# uc2950-v1.net
KiCad netlist of a schematic drawn in EAGLE
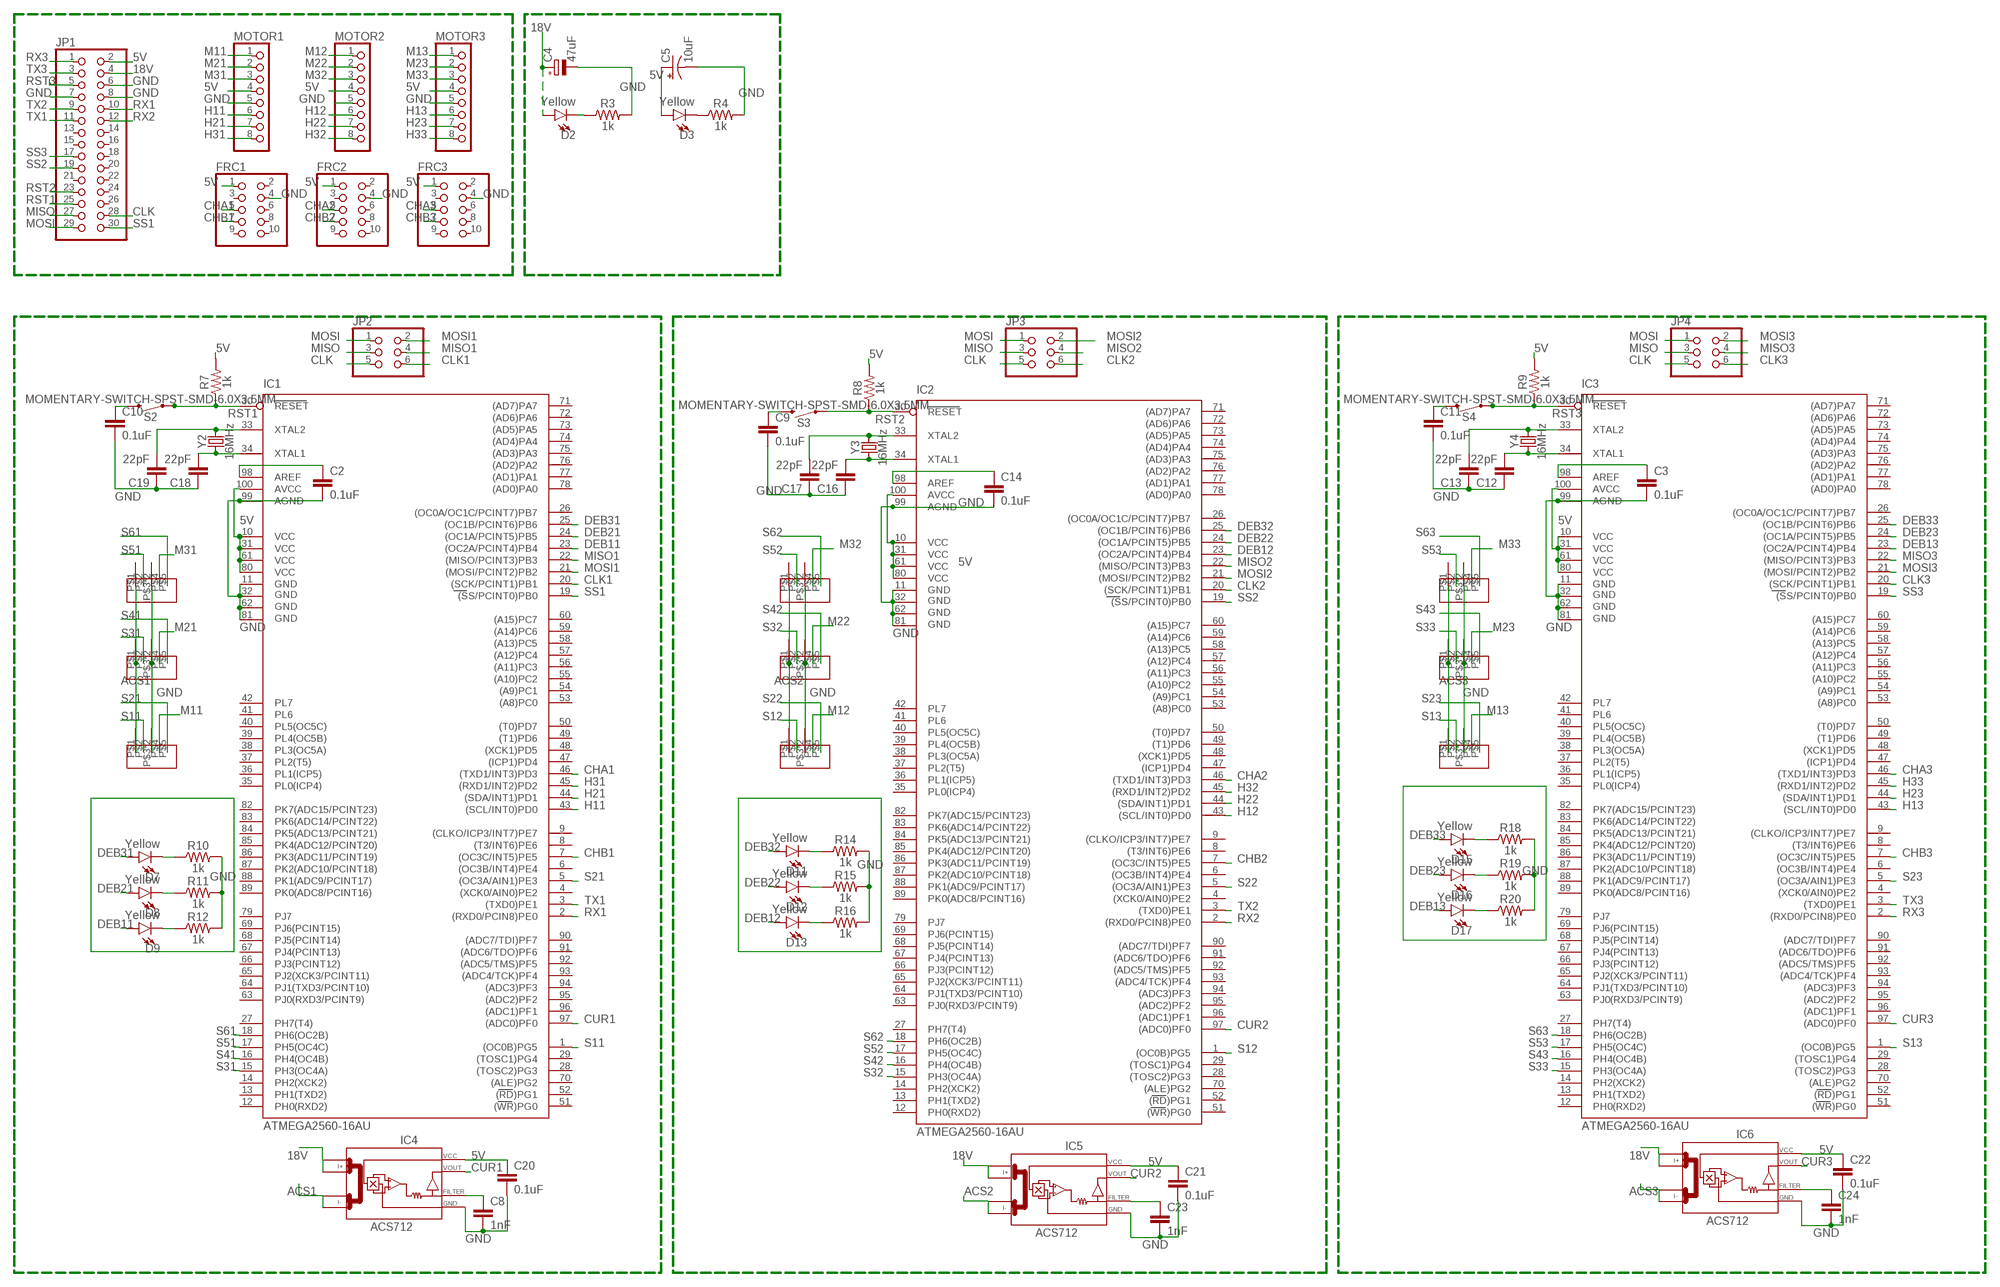
[diagram p0: schematic, sheet 1]

(export (version "E")
  (design (tool "Eeschema 10.0.6"))
  (components
    (comp (ref "C2")
      (value "0.1uF")
      (footprint "eagle-import:0603")
      (libsource (lib "eagle-import") (part "0.1UF-0603-25V-5%"))
    )
    (comp (ref "C3")
      (value "0.1uF")
      (footprint "eagle-import:0603")
      (libsource (lib "eagle-import") (part "0.1UF-0603-25V-5%"))
    )
    (comp (ref "C4")
      (value "47uF")
      (footprint "eagle-import:TAP5-60")
      (libsource (lib "eagle-import") (part "CPOL-EUTAP5-60"))
    )
    (comp (ref "C5")
      (value "10uF")
      (footprint "eagle-import:0603-POLAR")
      (libsource (lib "eagle-import") (part "10UF-POLAR-0603-6.3V-20%(TANT)"))
    )
    (comp (ref "C8")
      (value "1nF")
      (footprint "eagle-import:0603")
      (libsource (lib "eagle-import") (part "1.0NF/1000PF-0603-50V-10%"))
    )
    (comp (ref "C9")
      (value "0.1uF")
      (footprint "eagle-import:0603")
      (libsource (lib "eagle-import") (part "0.1UF-0603-25V-5%"))
    )
    (comp (ref "C10")
      (value "0.1uF")
      (footprint "eagle-import:0603")
      (libsource (lib "eagle-import") (part "0.1UF-0603-25V-5%"))
    )
    (comp (ref "C11")
      (value "0.1uF")
      (footprint "eagle-import:0603")
      (libsource (lib "eagle-import") (part "0.1UF-0603-25V-5%"))
    )
    (comp (ref "C12")
      (value "22pF")
      (footprint "eagle-import:0603")
      (libsource (lib "eagle-import") (part "22PF-0603-50V-5%"))
    )
    (comp (ref "C13")
      (value "22pF")
      (footprint "eagle-import:0603")
      (libsource (lib "eagle-import") (part "22PF-0603-50V-5%"))
    )
    (comp (ref "C14")
      (value "0.1uF")
      (footprint "eagle-import:0603")
      (libsource (lib "eagle-import") (part "0.1UF-0603-25V-5%"))
    )
    (comp (ref "C16")
      (value "22pF")
      (footprint "eagle-import:0603")
      (libsource (lib "eagle-import") (part "22PF-0603-50V-5%"))
    )
    (comp (ref "C17")
      (value "22pF")
      (footprint "eagle-import:0603")
      (libsource (lib "eagle-import") (part "22PF-0603-50V-5%"))
    )
    (comp (ref "C18")
      (value "22pF")
      (footprint "eagle-import:0603")
      (libsource (lib "eagle-import") (part "22PF-0603-50V-5%"))
    )
    (comp (ref "C19")
      (value "22pF")
      (footprint "eagle-import:0603")
      (libsource (lib "eagle-import") (part "22PF-0603-50V-5%"))
    )
    (comp (ref "C20")
      (value "0.1uF")
      (footprint "eagle-import:0603")
      (libsource (lib "eagle-import") (part "0.1UF-0603-25V-5%"))
    )
    (comp (ref "C21")
      (value "0.1uF")
      (footprint "eagle-import:0603")
      (libsource (lib "eagle-import") (part "0.1UF-0603-25V-5%"))
    )
    (comp (ref "C22")
      (value "0.1uF")
      (footprint "eagle-import:0603")
      (libsource (lib "eagle-import") (part "0.1UF-0603-25V-5%"))
    )
    (comp (ref "C23")
      (value "1nF")
      (footprint "eagle-import:0603")
      (libsource (lib "eagle-import") (part "1.0NF/1000PF-0603-50V-10%"))
    )
    (comp (ref "C24")
      (value "1nF")
      (footprint "eagle-import:0603")
      (libsource (lib "eagle-import") (part "1.0NF/1000PF-0603-50V-10%"))
    )
    (comp (ref "D2")
      (value "Yellow")
      (footprint "eagle-import:LED-0603")
      (libsource (lib "eagle-import") (part "LED-YELLOW0603"))
    )
    (comp (ref "D3")
      (value "Yellow")
      (footprint "eagle-import:LED-0603")
      (libsource (lib "eagle-import") (part "LED-YELLOW0603"))
    )
    (comp (ref "D7")
      (value "Yellow")
      (footprint "eagle-import:LED-0603")
      (libsource (lib "eagle-import") (part "LED-YELLOW0603"))
    )
    (comp (ref "D8")
      (value "Yellow")
      (footprint "eagle-import:LED-0603")
      (libsource (lib "eagle-import") (part "LED-YELLOW0603"))
    )
    (comp (ref "D9")
      (value "Yellow")
      (footprint "eagle-import:LED-0603")
      (libsource (lib "eagle-import") (part "LED-YELLOW0603"))
    )
    (comp (ref "D11")
      (value "Yellow")
      (footprint "eagle-import:LED-0603")
      (libsource (lib "eagle-import") (part "LED-YELLOW0603"))
    )
    (comp (ref "D12")
      (value "Yellow")
      (footprint "eagle-import:LED-0603")
      (libsource (lib "eagle-import") (part "LED-YELLOW0603"))
    )
    (comp (ref "D13")
      (value "Yellow")
      (footprint "eagle-import:LED-0603")
      (libsource (lib "eagle-import") (part "LED-YELLOW0603"))
    )
    (comp (ref "D15")
      (value "Yellow")
      (footprint "eagle-import:LED-0603")
      (libsource (lib "eagle-import") (part "LED-YELLOW0603"))
    )
    (comp (ref "D16")
      (value "Yellow")
      (footprint "eagle-import:LED-0603")
      (libsource (lib "eagle-import") (part "LED-YELLOW0603"))
    )
    (comp (ref "D17")
      (value "Yellow")
      (footprint "eagle-import:LED-0603")
      (libsource (lib "eagle-import") (part "LED-YELLOW0603"))
    )
    (comp (ref "FRC1")
      (value "PINHD-2X5")
      (footprint "eagle-import:2X05")
      (libsource (lib "eagle-import") (part "PINHD-2X5"))
    )
    (comp (ref "FRC2")
      (value "PINHD-2X5")
      (footprint "eagle-import:2X05")
      (libsource (lib "eagle-import") (part "PINHD-2X5"))
    )
    (comp (ref "FRC3")
      (value "PINHD-2X5")
      (footprint "eagle-import:2X05")
      (libsource (lib "eagle-import") (part "PINHD-2X5"))
    )
    (comp (ref "IC1")
      (value "ATMEGA2560-16AU")
      (footprint "eagle-import:TQFP100")
      (libsource (lib "eagle-import") (part "ATMEGAAU2560-16"))
    )
    (comp (ref "IC2")
      (value "ATMEGA2560-16AU")
      (footprint "eagle-import:TQFP100")
      (libsource (lib "eagle-import") (part "ATMEGAAU2560-16"))
    )
    (comp (ref "IC3")
      (value "ATMEGA2560-16AU")
      (footprint "eagle-import:TQFP100")
      (libsource (lib "eagle-import") (part "ATMEGAAU2560-16"))
    )
    (comp (ref "IC4")
      (value "ACS712")
      (footprint "eagle-import:SO08")
      (libsource (lib "eagle-import") (part "ACS712"))
    )
    (comp (ref "IC5")
      (value "ACS712")
      (footprint "eagle-import:SO08")
      (libsource (lib "eagle-import") (part "ACS712"))
    )
    (comp (ref "IC6")
      (value "ACS712")
      (footprint "eagle-import:SO08")
      (libsource (lib "eagle-import") (part "ACS712"))
    )
    (comp (ref "JP1")
      (value "PINHD-2X15/90")
      (footprint "eagle-import:2X15_90")
      (libsource (lib "eagle-import") (part "PINHD-2X15/90"))
    )
    (comp (ref "JP2")
      (value "PINHD-2X3")
      (footprint "eagle-import:2X03")
      (libsource (lib "eagle-import") (part "PINHD-2X3"))
    )
    (comp (ref "JP3")
      (value "PINHD-2X3")
      (footprint "eagle-import:2X03")
      (libsource (lib "eagle-import") (part "PINHD-2X3"))
    )
    (comp (ref "JP4")
      (value "PINHD-2X3")
      (footprint "eagle-import:2X03")
      (libsource (lib "eagle-import") (part "PINHD-2X3"))
    )
    (comp (ref "MIC1")
      (value "UC2950")
      (footprint "eagle-import:UC2950")
      (libsource (lib "eagle-import") (part "UC2950"))
    )
    (comp (ref "MIC2")
      (value "UC2950")
      (footprint "eagle-import:UC2950")
      (libsource (lib "eagle-import") (part "UC2950"))
    )
    (comp (ref "MIC3")
      (value "UC2950")
      (footprint "eagle-import:UC2950")
      (libsource (lib "eagle-import") (part "UC2950"))
    )
    (comp (ref "MIC4")
      (value "UC2950")
      (footprint "eagle-import:UC2950")
      (libsource (lib "eagle-import") (part "UC2950"))
    )
    (comp (ref "MIC5")
      (value "UC2950")
      (footprint "eagle-import:UC2950")
      (libsource (lib "eagle-import") (part "UC2950"))
    )
    (comp (ref "MIC6")
      (value "UC2950")
      (footprint "eagle-import:UC2950")
      (libsource (lib "eagle-import") (part "UC2950"))
    )
    (comp (ref "MIC7")
      (value "UC2950")
      (footprint "eagle-import:UC2950")
      (libsource (lib "eagle-import") (part "UC2950"))
    )
    (comp (ref "MIC8")
      (value "UC2950")
      (footprint "eagle-import:UC2950")
      (libsource (lib "eagle-import") (part "UC2950"))
    )
    (comp (ref "MIC9")
      (value "UC2950")
      (footprint "eagle-import:UC2950")
      (libsource (lib "eagle-import") (part "UC2950"))
    )
    (comp (ref "MOTOR1")
      (value "PINHD-1X8")
      (footprint "eagle-import:1X08")
      (libsource (lib "eagle-import") (part "PINHD-1X8"))
    )
    (comp (ref "MOTOR2")
      (value "PINHD-1X8")
      (footprint "eagle-import:1X08")
      (libsource (lib "eagle-import") (part "PINHD-1X8"))
    )
    (comp (ref "MOTOR3")
      (value "PINHD-1X8")
      (footprint "eagle-import:1X08")
      (libsource (lib "eagle-import") (part "PINHD-1X8"))
    )
    (comp (ref "R3")
      (value "1k")
      (footprint "eagle-import:0603")
      (libsource (lib "eagle-import") (part "1KOHM-0603-1/10W-1%"))
    )
    (comp (ref "R4")
      (value "1k")
      (footprint "eagle-import:0603")
      (libsource (lib "eagle-import") (part "1KOHM-0603-1/10W-1%"))
    )
    (comp (ref "R7")
      (value "1k")
      (footprint "eagle-import:0603")
      (libsource (lib "eagle-import") (part "1KOHM-0603-1/10W-1%"))
    )
    (comp (ref "R8")
      (value "1k")
      (footprint "eagle-import:0603")
      (libsource (lib "eagle-import") (part "1KOHM-0603-1/10W-1%"))
    )
    (comp (ref "R9")
      (value "1k")
      (footprint "eagle-import:0603")
      (libsource (lib "eagle-import") (part "1KOHM-0603-1/10W-1%"))
    )
    (comp (ref "R10")
      (value "1k")
      (footprint "eagle-import:0603")
      (libsource (lib "eagle-import") (part "1KOHM-0603-1/10W-1%"))
    )
    (comp (ref "R11")
      (value "1k")
      (footprint "eagle-import:0603")
      (libsource (lib "eagle-import") (part "1KOHM-0603-1/10W-1%"))
    )
    (comp (ref "R12")
      (value "1k")
      (footprint "eagle-import:0603")
      (libsource (lib "eagle-import") (part "1KOHM-0603-1/10W-1%"))
    )
    (comp (ref "R14")
      (value "1k")
      (footprint "eagle-import:0603")
      (libsource (lib "eagle-import") (part "1KOHM-0603-1/10W-1%"))
    )
    (comp (ref "R15")
      (value "1k")
      (footprint "eagle-import:0603")
      (libsource (lib "eagle-import") (part "1KOHM-0603-1/10W-1%"))
    )
    (comp (ref "R16")
      (value "1k")
      (footprint "eagle-import:0603")
      (libsource (lib "eagle-import") (part "1KOHM-0603-1/10W-1%"))
    )
    (comp (ref "R18")
      (value "1k")
      (footprint "eagle-import:0603")
      (libsource (lib "eagle-import") (part "1KOHM-0603-1/10W-1%"))
    )
    (comp (ref "R19")
      (value "1k")
      (footprint "eagle-import:0603")
      (libsource (lib "eagle-import") (part "1KOHM-0603-1/10W-1%"))
    )
    (comp (ref "R20")
      (value "1k")
      (footprint "eagle-import:0603")
      (libsource (lib "eagle-import") (part "1KOHM-0603-1/10W-1%"))
    )
    (comp (ref "S2")
      (value "MOMENTARY-SWITCH-SPST-SMD-6.0X3.5MM")
      (footprint "eagle-import:TACTILE_SWITCH_SMD_6.0X3.5MM")
      (libsource (lib "eagle-import") (part "MOMENTARY-SWITCH-SPST-SMD-6.0X3.5MM"))
    )
    (comp (ref "S3")
      (value "MOMENTARY-SWITCH-SPST-SMD-6.0X3.5MM")
      (footprint "eagle-import:TACTILE_SWITCH_SMD_6.0X3.5MM")
      (libsource (lib "eagle-import") (part "MOMENTARY-SWITCH-SPST-SMD-6.0X3.5MM"))
    )
    (comp (ref "S4")
      (value "MOMENTARY-SWITCH-SPST-SMD-6.0X3.5MM")
      (footprint "eagle-import:TACTILE_SWITCH_SMD_6.0X3.5MM")
      (libsource (lib "eagle-import") (part "MOMENTARY-SWITCH-SPST-SMD-6.0X3.5MM"))
    )
    (comp (ref "Y2")
      (value "16MHz")
      (footprint "eagle-import:CRYSTAL-SMD-5X3.2-4PAD")
      (libsource (lib "eagle-import") (part "CRYSTAL-16MHZSMD-5X3.2"))
    )
    (comp (ref "Y3")
      (value "16MHz")
      (footprint "eagle-import:CRYSTAL-SMD-5X3.2-4PAD")
      (libsource (lib "eagle-import") (part "CRYSTAL-16MHZSMD-5X3.2"))
    )
    (comp (ref "Y4")
      (value "16MHz")
      (footprint "eagle-import:CRYSTAL-SMD-5X3.2-4PAD")
      (libsource (lib "eagle-import") (part "CRYSTAL-16MHZSMD-5X3.2"))
    )
  )
  (nets
    (net (code "1") (name "/5V") (class "Default")
      (node (ref "C20") (pin "1") (pinfunction "1_1") (pintype "passive"))
      (node (ref "C21") (pin "1") (pinfunction "1_1") (pintype "passive"))
      (node (ref "C22") (pin "1") (pinfunction "1_1") (pintype "passive"))
      (node (ref "C5") (pin "+") (pinfunction "+_+") (pintype "passive"))
      (node (ref "D3") (pin "A") (pinfunction "A_A") (pintype "passive"))
      (node (ref "FRC1") (pin "1") (pinfunction "1_1") (pintype "passive"))
      (node (ref "FRC2") (pin "1") (pinfunction "1_1") (pintype "passive"))
      (node (ref "FRC3") (pin "1") (pinfunction "1_1") (pintype "passive"))
      (node (ref "IC1") (pin "10") (pinfunction "VCC_10") (pintype "power_in"))
      (node (ref "IC1") (pin "100") (pinfunction "AVCC_100") (pintype "power_in"))
      (node (ref "IC1") (pin "31") (pinfunction "VCC1_31") (pintype "power_in"))
      (node (ref "IC1") (pin "61") (pinfunction "VCC2_61") (pintype "power_in"))
      (node (ref "IC1") (pin "80") (pinfunction "VCC3_80") (pintype "power_in"))
      (node (ref "IC2") (pin "10") (pinfunction "VCC_10") (pintype "power_in"))
      (node (ref "IC2") (pin "100") (pinfunction "AVCC_100") (pintype "power_in"))
      (node (ref "IC2") (pin "31") (pinfunction "VCC1_31") (pintype "power_in"))
      (node (ref "IC2") (pin "61") (pinfunction "VCC2_61") (pintype "power_in"))
      (node (ref "IC2") (pin "80") (pinfunction "VCC3_80") (pintype "power_in"))
      (node (ref "IC3") (pin "10") (pinfunction "VCC_10") (pintype "power_in"))
      (node (ref "IC3") (pin "100") (pinfunction "AVCC_100") (pintype "power_in"))
      (node (ref "IC3") (pin "31") (pinfunction "VCC1_31") (pintype "power_in"))
      (node (ref "IC3") (pin "61") (pinfunction "VCC2_61") (pintype "power_in"))
      (node (ref "IC3") (pin "80") (pinfunction "VCC3_80") (pintype "power_in"))
      (node (ref "IC4") (pin "8") (pinfunction "VCC_8") (pintype "power_in"))
      (node (ref "IC5") (pin "8") (pinfunction "VCC_8") (pintype "power_in"))
      (node (ref "IC6") (pin "8") (pinfunction "VCC_8") (pintype "power_in"))
      (node (ref "JP1") (pin "2") (pinfunction "2_2") (pintype "passive"))
      (node (ref "MOTOR1") (pin "4") (pinfunction "4_4") (pintype "passive"))
      (node (ref "MOTOR2") (pin "4") (pinfunction "4_4") (pintype "passive"))
      (node (ref "MOTOR3") (pin "4") (pinfunction "4_4") (pintype "passive"))
      (node (ref "R7") (pin "2") (pinfunction "2_2") (pintype "passive"))
      (node (ref "R8") (pin "2") (pinfunction "2_2") (pintype "passive"))
      (node (ref "R9") (pin "2") (pinfunction "2_2") (pintype "passive"))
    )
    (net (code "2") (name "/18V") (class "Default")
      (node (ref "C4") (pin "+") (pinfunction "+_+") (pintype "passive"))
      (node (ref "D2") (pin "A") (pinfunction "A_A") (pintype "passive"))
      (node (ref "IC4") (pin "1") (pinfunction "I+_0_1") (pintype "bidirectional"))
      (node (ref "IC5") (pin "1") (pinfunction "I+_0_1") (pintype "bidirectional"))
      (node (ref "IC6") (pin "1") (pinfunction "I+_0_1") (pintype "bidirectional"))
      (node (ref "JP1") (pin "4") (pinfunction "4_4") (pintype "passive"))
    )
    (net (code "3") (name "/ACS1") (class "Default")
      (node (ref "IC4") (pin "3") (pinfunction "I-_0_3") (pintype "bidirectional"))
      (node (ref "MIC1") (pin "P$1") (pinfunction "P$1_P$1") (pintype "bidirectional"))
      (node (ref "MIC2") (pin "P$1") (pinfunction "P$1_P$1") (pintype "bidirectional"))
      (node (ref "MIC3") (pin "P$1") (pinfunction "P$1_P$1") (pintype "bidirectional"))
    )
    (net (code "4") (name "/ACS2") (class "Default")
      (node (ref "IC5") (pin "3") (pinfunction "I-_0_3") (pintype "bidirectional"))
      (node (ref "MIC4") (pin "P$1") (pinfunction "P$1_P$1") (pintype "bidirectional"))
      (node (ref "MIC5") (pin "P$1") (pinfunction "P$1_P$1") (pintype "bidirectional"))
      (node (ref "MIC6") (pin "P$1") (pinfunction "P$1_P$1") (pintype "bidirectional"))
    )
    (net (code "5") (name "/ACS3") (class "Default")
      (node (ref "IC6") (pin "3") (pinfunction "I-_0_3") (pintype "bidirectional"))
      (node (ref "MIC7") (pin "P$1") (pinfunction "P$1_P$1") (pintype "bidirectional"))
      (node (ref "MIC8") (pin "P$1") (pinfunction "P$1_P$1") (pintype "bidirectional"))
      (node (ref "MIC9") (pin "P$1") (pinfunction "P$1_P$1") (pintype "bidirectional"))
    )
    (net (code "6") (name "/CHA1") (class "Default")
      (node (ref "FRC1") (pin "5") (pinfunction "5_5") (pintype "passive"))
      (node (ref "IC1") (pin "46") (pinfunction "(TXD1/INT3)PD3_46") (pintype "bidirectional"))
    )
    (net (code "7") (name "/CHA2") (class "Default")
      (node (ref "FRC2") (pin "5") (pinfunction "5_5") (pintype "passive"))
      (node (ref "IC2") (pin "46") (pinfunction "(TXD1/INT3)PD3_46") (pintype "bidirectional"))
    )
    (net (code "8") (name "/CHA3") (class "Default")
      (node (ref "FRC3") (pin "5") (pinfunction "5_5") (pintype "passive"))
      (node (ref "IC3") (pin "46") (pinfunction "(TXD1/INT3)PD3_46") (pintype "bidirectional"))
    )
    (net (code "9") (name "/CHB1") (class "Default")
      (node (ref "FRC1") (pin "7") (pinfunction "7_7") (pintype "passive"))
      (node (ref "IC1") (pin "7") (pinfunction "(OC3C/INT5)PE5_7") (pintype "bidirectional"))
    )
    (net (code "10") (name "/CHB2") (class "Default")
      (node (ref "FRC2") (pin "7") (pinfunction "7_7") (pintype "passive"))
      (node (ref "IC2") (pin "7") (pinfunction "(OC3C/INT5)PE5_7") (pintype "bidirectional"))
    )
    (net (code "11") (name "/CHB3") (class "Default")
      (node (ref "FRC3") (pin "7") (pinfunction "7_7") (pintype "passive"))
      (node (ref "IC3") (pin "7") (pinfunction "(OC3C/INT5)PE5_7") (pintype "bidirectional"))
    )
    (net (code "12") (name "/CLK") (class "Default")
      (node (ref "JP1") (pin "28") (pinfunction "28_28") (pintype "passive"))
      (node (ref "JP2") (pin "5") (pinfunction "5_5") (pintype "passive"))
      (node (ref "JP3") (pin "5") (pinfunction "5_5") (pintype "passive"))
      (node (ref "JP4") (pin "5") (pinfunction "5_5") (pintype "passive"))
    )
    (net (code "13") (name "/CLK1") (class "Default")
      (node (ref "IC1") (pin "20") (pinfunction "(SCK/PCINT1)PB1_20") (pintype "bidirectional"))
      (node (ref "JP2") (pin "6") (pinfunction "6_6") (pintype "passive"))
    )
    (net (code "14") (name "/CLK2") (class "Default")
      (node (ref "IC2") (pin "20") (pinfunction "(SCK/PCINT1)PB1_20") (pintype "bidirectional"))
      (node (ref "JP3") (pin "6") (pinfunction "6_6") (pintype "passive"))
    )
    (net (code "15") (name "/CLK3") (class "Default")
      (node (ref "IC3") (pin "20") (pinfunction "(SCK/PCINT1)PB1_20") (pintype "bidirectional"))
      (node (ref "JP4") (pin "6") (pinfunction "6_6") (pintype "passive"))
    )
    (net (code "16") (name "/CUR1") (class "Default")
      (node (ref "IC1") (pin "97") (pinfunction "(ADC0)PF0_97") (pintype "bidirectional"))
      (node (ref "IC4") (pin "7") (pinfunction "VOUT_7") (pintype "output"))
    )
    (net (code "17") (name "/CUR2") (class "Default")
      (node (ref "IC2") (pin "97") (pinfunction "(ADC0)PF0_97") (pintype "bidirectional"))
      (node (ref "IC5") (pin "7") (pinfunction "VOUT_7") (pintype "output"))
    )
    (net (code "18") (name "/CUR3") (class "Default")
      (node (ref "IC3") (pin "97") (pinfunction "(ADC0)PF0_97") (pintype "bidirectional"))
      (node (ref "IC6") (pin "7") (pinfunction "VOUT_7") (pintype "output"))
    )
    (net (code "19") (name "/DEB11") (class "Default")
      (node (ref "D9") (pin "A") (pinfunction "A_A") (pintype "passive"))
      (node (ref "IC1") (pin "23") (pinfunction "(OC2A/PCINT4)PB4_23") (pintype "bidirectional"))
    )
    (net (code "20") (name "/DEB12") (class "Default")
      (node (ref "D13") (pin "A") (pinfunction "A_A") (pintype "passive"))
      (node (ref "IC2") (pin "23") (pinfunction "(OC2A/PCINT4)PB4_23") (pintype "bidirectional"))
    )
    (net (code "21") (name "/DEB13") (class "Default")
      (node (ref "D17") (pin "A") (pinfunction "A_A") (pintype "passive"))
      (node (ref "IC3") (pin "23") (pinfunction "(OC2A/PCINT4)PB4_23") (pintype "bidirectional"))
    )
    (net (code "22") (name "/DEB21") (class "Default")
      (node (ref "D8") (pin "A") (pinfunction "A_A") (pintype "passive"))
      (node (ref "IC1") (pin "24") (pinfunction "(OC1A/PCINT5)PB5_24") (pintype "bidirectional"))
    )
    (net (code "23") (name "/DEB22") (class "Default")
      (node (ref "D12") (pin "A") (pinfunction "A_A") (pintype "passive"))
      (node (ref "IC2") (pin "24") (pinfunction "(OC1A/PCINT5)PB5_24") (pintype "bidirectional"))
    )
    (net (code "24") (name "/DEB23") (class "Default")
      (node (ref "D16") (pin "A") (pinfunction "A_A") (pintype "passive"))
      (node (ref "IC3") (pin "24") (pinfunction "(OC1A/PCINT5)PB5_24") (pintype "bidirectional"))
    )
    (net (code "25") (name "/DEB31") (class "Default")
      (node (ref "D7") (pin "A") (pinfunction "A_A") (pintype "passive"))
      (node (ref "IC1") (pin "25") (pinfunction "(OC1B/PCINT6)PB6_25") (pintype "bidirectional"))
    )
    (net (code "26") (name "/DEB32") (class "Default")
      (node (ref "D11") (pin "A") (pinfunction "A_A") (pintype "passive"))
      (node (ref "IC2") (pin "25") (pinfunction "(OC1B/PCINT6)PB6_25") (pintype "bidirectional"))
    )
    (net (code "27") (name "/DEB33") (class "Default")
      (node (ref "D15") (pin "A") (pinfunction "A_A") (pintype "passive"))
      (node (ref "IC3") (pin "25") (pinfunction "(OC1B/PCINT6)PB6_25") (pintype "bidirectional"))
    )
    (net (code "28") (name "/GND") (class "Default")
      (node (ref "C10") (pin "2") (pinfunction "2_2") (pintype "passive"))
      (node (ref "C11") (pin "2") (pinfunction "2_2") (pintype "passive"))
      (node (ref "C12") (pin "1") (pinfunction "1_1") (pintype "passive"))
      (node (ref "C13") (pin "1") (pinfunction "1_1") (pintype "passive"))
      (node (ref "C14") (pin "2") (pinfunction "2_2") (pintype "passive"))
      (node (ref "C16") (pin "1") (pinfunction "1_1") (pintype "passive"))
      (node (ref "C17") (pin "1") (pinfunction "1_1") (pintype "passive"))
      (node (ref "C18") (pin "1") (pinfunction "1_1") (pintype "passive"))
      (node (ref "C19") (pin "1") (pinfunction "1_1") (pintype "passive"))
      (node (ref "C2") (pin "2") (pinfunction "2_2") (pintype "passive"))
      (node (ref "C20") (pin "2") (pinfunction "2_2") (pintype "passive"))
      (node (ref "C21") (pin "2") (pinfunction "2_2") (pintype "passive"))
      (node (ref "C22") (pin "2") (pinfunction "2_2") (pintype "passive"))
      (node (ref "C23") (pin "2") (pinfunction "2_2") (pintype "passive"))
      (node (ref "C24") (pin "2") (pinfunction "2_2") (pintype "passive"))
      (node (ref "C3") (pin "2") (pinfunction "2_2") (pintype "passive"))
      (node (ref "C4") (pin "-") (pinfunction "-_-") (pintype "passive"))
      (node (ref "C5") (pin "-") (pinfunction "-_-") (pintype "passive"))
      (node (ref "C8") (pin "2") (pinfunction "2_2") (pintype "passive"))
      (node (ref "C9") (pin "2") (pinfunction "2_2") (pintype "passive"))
      (node (ref "FRC1") (pin "4") (pinfunction "4_4") (pintype "passive"))
      (node (ref "FRC2") (pin "4") (pinfunction "4_4") (pintype "passive"))
      (node (ref "FRC3") (pin "4") (pinfunction "4_4") (pintype "passive"))
      (node (ref "IC1") (pin "11") (pinfunction "GND_11") (pintype "power_in"))
      (node (ref "IC1") (pin "32") (pinfunction "GND1_32") (pintype "power_in"))
      (node (ref "IC1") (pin "62") (pinfunction "GND2_62") (pintype "power_in"))
      (node (ref "IC1") (pin "81") (pinfunction "GND3_81") (pintype "power_in"))
      (node (ref "IC1") (pin "99") (pinfunction "AGND_99") (pintype "power_in"))
      (node (ref "IC2") (pin "11") (pinfunction "GND_11") (pintype "power_in"))
      (node (ref "IC2") (pin "32") (pinfunction "GND1_32") (pintype "power_in"))
      (node (ref "IC2") (pin "62") (pinfunction "GND2_62") (pintype "power_in"))
      (node (ref "IC2") (pin "81") (pinfunction "GND3_81") (pintype "power_in"))
      (node (ref "IC2") (pin "99") (pinfunction "AGND_99") (pintype "power_in"))
      (node (ref "IC3") (pin "11") (pinfunction "GND_11") (pintype "power_in"))
      (node (ref "IC3") (pin "32") (pinfunction "GND1_32") (pintype "power_in"))
      (node (ref "IC3") (pin "62") (pinfunction "GND2_62") (pintype "power_in"))
      (node (ref "IC3") (pin "81") (pinfunction "GND3_81") (pintype "power_in"))
      (node (ref "IC3") (pin "99") (pinfunction "AGND_99") (pintype "power_in"))
      (node (ref "IC4") (pin "5") (pinfunction "GND_5") (pintype "power_in"))
      (node (ref "IC5") (pin "5") (pinfunction "GND_5") (pintype "power_in"))
      (node (ref "IC6") (pin "5") (pinfunction "GND_5") (pintype "power_in"))
      (node (ref "JP1") (pin "6") (pinfunction "6_6") (pintype "passive"))
      (node (ref "JP1") (pin "7") (pinfunction "7_7") (pintype "passive"))
      (node (ref "JP1") (pin "8") (pinfunction "8_8") (pintype "passive"))
      (node (ref "MIC1") (pin "P$3") (pinfunction "P$3_P$3") (pintype "bidirectional"))
      (node (ref "MIC1") (pin "P$6") (pinfunction "P$3_P$6") (pintype "bidirectional"))
      (node (ref "MIC2") (pin "P$3") (pinfunction "P$3_P$3") (pintype "bidirectional"))
      (node (ref "MIC2") (pin "P$6") (pinfunction "P$3_P$6") (pintype "bidirectional"))
      (node (ref "MIC3") (pin "P$3") (pinfunction "P$3_P$3") (pintype "bidirectional"))
      (node (ref "MIC3") (pin "P$6") (pinfunction "P$3_P$6") (pintype "bidirectional"))
      (node (ref "MIC4") (pin "P$3") (pinfunction "P$3_P$3") (pintype "bidirectional"))
      (node (ref "MIC4") (pin "P$6") (pinfunction "P$3_P$6") (pintype "bidirectional"))
      (node (ref "MIC5") (pin "P$3") (pinfunction "P$3_P$3") (pintype "bidirectional"))
      (node (ref "MIC5") (pin "P$6") (pinfunction "P$3_P$6") (pintype "bidirectional"))
      (node (ref "MIC6") (pin "P$3") (pinfunction "P$3_P$3") (pintype "bidirectional"))
      (node (ref "MIC6") (pin "P$6") (pinfunction "P$3_P$6") (pintype "bidirectional"))
      (node (ref "MIC7") (pin "P$3") (pinfunction "P$3_P$3") (pintype "bidirectional"))
      (node (ref "MIC7") (pin "P$6") (pinfunction "P$3_P$6") (pintype "bidirectional"))
      (node (ref "MIC8") (pin "P$3") (pinfunction "P$3_P$3") (pintype "bidirectional"))
      (node (ref "MIC8") (pin "P$6") (pinfunction "P$3_P$6") (pintype "bidirectional"))
      (node (ref "MIC9") (pin "P$3") (pinfunction "P$3_P$3") (pintype "bidirectional"))
      (node (ref "MIC9") (pin "P$6") (pinfunction "P$3_P$6") (pintype "bidirectional"))
      (node (ref "MOTOR1") (pin "5") (pinfunction "5_5") (pintype "passive"))
      (node (ref "MOTOR2") (pin "5") (pinfunction "5_5") (pintype "passive"))
      (node (ref "MOTOR3") (pin "5") (pinfunction "5_5") (pintype "passive"))
      (node (ref "R10") (pin "2") (pinfunction "2_2") (pintype "passive"))
      (node (ref "R11") (pin "2") (pinfunction "2_2") (pintype "passive"))
      (node (ref "R12") (pin "2") (pinfunction "2_2") (pintype "passive"))
      (node (ref "R14") (pin "2") (pinfunction "2_2") (pintype "passive"))
      (node (ref "R15") (pin "2") (pinfunction "2_2") (pintype "passive"))
      (node (ref "R16") (pin "2") (pinfunction "2_2") (pintype "passive"))
      (node (ref "R18") (pin "2") (pinfunction "2_2") (pintype "passive"))
      (node (ref "R19") (pin "2") (pinfunction "2_2") (pintype "passive"))
      (node (ref "R20") (pin "2") (pinfunction "2_2") (pintype "passive"))
      (node (ref "R3") (pin "2") (pinfunction "2_2") (pintype "passive"))
      (node (ref "R4") (pin "2") (pinfunction "2_2") (pintype "passive"))
    )
    (net (code "29") (name "/H11") (class "Default")
      (node (ref "IC1") (pin "43") (pinfunction "(SCL/INT0)PD0_43") (pintype "bidirectional"))
      (node (ref "MOTOR1") (pin "6") (pinfunction "6_6") (pintype "passive"))
    )
    (net (code "30") (name "/H12") (class "Default")
      (node (ref "IC2") (pin "43") (pinfunction "(SCL/INT0)PD0_43") (pintype "bidirectional"))
      (node (ref "MOTOR2") (pin "6") (pinfunction "6_6") (pintype "passive"))
    )
    (net (code "31") (name "/H13") (class "Default")
      (node (ref "IC3") (pin "43") (pinfunction "(SCL/INT0)PD0_43") (pintype "bidirectional"))
      (node (ref "MOTOR3") (pin "6") (pinfunction "6_6") (pintype "passive"))
    )
    (net (code "32") (name "/H21") (class "Default")
      (node (ref "IC1") (pin "44") (pinfunction "(SDA/INT1)PD1_44") (pintype "bidirectional"))
      (node (ref "MOTOR1") (pin "7") (pinfunction "7_7") (pintype "passive"))
    )
    (net (code "33") (name "/H22") (class "Default")
      (node (ref "IC2") (pin "44") (pinfunction "(SDA/INT1)PD1_44") (pintype "bidirectional"))
      (node (ref "MOTOR2") (pin "7") (pinfunction "7_7") (pintype "passive"))
    )
    (net (code "34") (name "/H23") (class "Default")
      (node (ref "IC3") (pin "44") (pinfunction "(SDA/INT1)PD1_44") (pintype "bidirectional"))
      (node (ref "MOTOR3") (pin "7") (pinfunction "7_7") (pintype "passive"))
    )
    (net (code "35") (name "/H31") (class "Default")
      (node (ref "IC1") (pin "45") (pinfunction "(RXD1/INT2)PD2_45") (pintype "bidirectional"))
      (node (ref "MOTOR1") (pin "8") (pinfunction "8_8") (pintype "passive"))
    )
    (net (code "36") (name "/H32") (class "Default")
      (node (ref "IC2") (pin "45") (pinfunction "(RXD1/INT2)PD2_45") (pintype "bidirectional"))
      (node (ref "MOTOR2") (pin "8") (pinfunction "8_8") (pintype "passive"))
    )
    (net (code "37") (name "/H33") (class "Default")
      (node (ref "IC3") (pin "45") (pinfunction "(RXD1/INT2)PD2_45") (pintype "bidirectional"))
      (node (ref "MOTOR3") (pin "8") (pinfunction "8_8") (pintype "passive"))
    )
    (net (code "38") (name "/M11") (class "Default")
      (node (ref "MIC3") (pin "P$4") (pinfunction "P$4_P$4") (pintype "bidirectional"))
      (node (ref "MOTOR1") (pin "1") (pinfunction "1_1") (pintype "passive"))
    )
    (net (code "39") (name "/M12") (class "Default")
      (node (ref "MIC6") (pin "P$4") (pinfunction "P$4_P$4") (pintype "bidirectional"))
      (node (ref "MOTOR2") (pin "1") (pinfunction "1_1") (pintype "passive"))
    )
    (net (code "40") (name "/M13") (class "Default")
      (node (ref "MIC7") (pin "P$4") (pinfunction "P$4_P$4") (pintype "bidirectional"))
      (node (ref "MOTOR3") (pin "1") (pinfunction "1_1") (pintype "passive"))
    )
    (net (code "41") (name "/M21") (class "Default")
      (node (ref "MIC2") (pin "P$4") (pinfunction "P$4_P$4") (pintype "bidirectional"))
      (node (ref "MOTOR1") (pin "2") (pinfunction "2_2") (pintype "passive"))
    )
    (net (code "42") (name "/M22") (class "Default")
      (node (ref "MIC5") (pin "P$4") (pinfunction "P$4_P$4") (pintype "bidirectional"))
      (node (ref "MOTOR2") (pin "2") (pinfunction "2_2") (pintype "passive"))
    )
    (net (code "43") (name "/M23") (class "Default")
      (node (ref "MIC8") (pin "P$4") (pinfunction "P$4_P$4") (pintype "bidirectional"))
      (node (ref "MOTOR3") (pin "2") (pinfunction "2_2") (pintype "passive"))
    )
    (net (code "44") (name "/M31") (class "Default")
      (node (ref "MIC1") (pin "P$4") (pinfunction "P$4_P$4") (pintype "bidirectional"))
      (node (ref "MOTOR1") (pin "3") (pinfunction "3_3") (pintype "passive"))
    )
    (net (code "45") (name "/M32") (class "Default")
      (node (ref "MIC4") (pin "P$4") (pinfunction "P$4_P$4") (pintype "bidirectional"))
      (node (ref "MOTOR2") (pin "3") (pinfunction "3_3") (pintype "passive"))
    )
    (net (code "46") (name "/M33") (class "Default")
      (node (ref "MIC9") (pin "P$4") (pinfunction "P$4_P$4") (pintype "bidirectional"))
      (node (ref "MOTOR3") (pin "3") (pinfunction "3_3") (pintype "passive"))
    )
    (net (code "47") (name "/MISO") (class "Default")
      (node (ref "JP1") (pin "27") (pinfunction "27_27") (pintype "passive"))
      (node (ref "JP2") (pin "3") (pinfunction "3_3") (pintype "passive"))
      (node (ref "JP3") (pin "3") (pinfunction "3_3") (pintype "passive"))
      (node (ref "JP4") (pin "3") (pinfunction "3_3") (pintype "passive"))
    )
    (net (code "48") (name "/MISO1") (class "Default")
      (node (ref "IC1") (pin "22") (pinfunction "(MISO/PCINT3)PB3_22") (pintype "bidirectional"))
      (node (ref "JP2") (pin "4") (pinfunction "4_4") (pintype "passive"))
    )
    (net (code "49") (name "/MISO2") (class "Default")
      (node (ref "IC2") (pin "22") (pinfunction "(MISO/PCINT3)PB3_22") (pintype "bidirectional"))
      (node (ref "JP3") (pin "4") (pinfunction "4_4") (pintype "passive"))
    )
    (net (code "50") (name "/MISO3") (class "Default")
      (node (ref "IC3") (pin "22") (pinfunction "(MISO/PCINT3)PB3_22") (pintype "bidirectional"))
      (node (ref "JP4") (pin "4") (pinfunction "4_4") (pintype "passive"))
    )
    (net (code "51") (name "/MOSI") (class "Default")
      (node (ref "JP1") (pin "29") (pinfunction "29_29") (pintype "passive"))
      (node (ref "JP2") (pin "1") (pinfunction "1_1") (pintype "passive"))
      (node (ref "JP3") (pin "1") (pinfunction "1_1") (pintype "passive"))
      (node (ref "JP4") (pin "1") (pinfunction "1_1") (pintype "passive"))
    )
    (net (code "52") (name "/MOSI1") (class "Default")
      (node (ref "IC1") (pin "21") (pinfunction "(MOSI/PCINT2)PB2_21") (pintype "bidirectional"))
      (node (ref "JP2") (pin "2") (pinfunction "2_2") (pintype "passive"))
    )
    (net (code "53") (name "/MOSI2") (class "Default")
      (node (ref "IC2") (pin "21") (pinfunction "(MOSI/PCINT2)PB2_21") (pintype "bidirectional"))
      (node (ref "JP3") (pin "2") (pinfunction "2_2") (pintype "passive"))
    )
    (net (code "54") (name "/MOSI3") (class "Default")
      (node (ref "IC3") (pin "21") (pinfunction "(MOSI/PCINT2)PB2_21") (pintype "bidirectional"))
      (node (ref "JP4") (pin "2") (pinfunction "2_2") (pintype "passive"))
    )
    (net (code "55") (name "/RST1") (class "Default")
      (node (ref "IC1") (pin "30") (pinfunction "RESET_30") (pintype "input"))
      (node (ref "JP1") (pin "25") (pinfunction "25_25") (pintype "passive"))
      (node (ref "R7") (pin "1") (pinfunction "1_1") (pintype "passive"))
      (node (ref "S2") (pin "1") (pinfunction "1_1") (pintype "passive"))
    )
    (net (code "56") (name "/RST2") (class "Default")
      (node (ref "IC2") (pin "30") (pinfunction "RESET_30") (pintype "input"))
      (node (ref "JP1") (pin "23") (pinfunction "23_23") (pintype "passive"))
      (node (ref "R8") (pin "1") (pinfunction "1_1") (pintype "passive"))
      (node (ref "S3") (pin "1") (pinfunction "1_1") (pintype "passive"))
    )
    (net (code "57") (name "/RST3") (class "Default")
      (node (ref "IC3") (pin "30") (pinfunction "RESET_30") (pintype "input"))
      (node (ref "JP1") (pin "5") (pinfunction "5_5") (pintype "passive"))
      (node (ref "R9") (pin "1") (pinfunction "1_1") (pintype "passive"))
      (node (ref "S4") (pin "1") (pinfunction "1_1") (pintype "passive"))
    )
    (net (code "58") (name "/RX1") (class "Default")
      (node (ref "IC1") (pin "2") (pinfunction "(RXD0/PCIN8)PE0_2") (pintype "bidirectional"))
      (node (ref "JP1") (pin "10") (pinfunction "10_10") (pintype "passive"))
    )
    (net (code "59") (name "/RX2") (class "Default")
      (node (ref "IC2") (pin "2") (pinfunction "(RXD0/PCIN8)PE0_2") (pintype "bidirectional"))
      (node (ref "JP1") (pin "12") (pinfunction "12_12") (pintype "passive"))
    )
    (net (code "60") (name "/RX3") (class "Default")
      (node (ref "IC3") (pin "2") (pinfunction "(RXD0/PCIN8)PE0_2") (pintype "bidirectional"))
      (node (ref "JP1") (pin "1") (pinfunction "1_1") (pintype "passive"))
    )
    (net (code "61") (name "/S11") (class "Default")
      (node (ref "IC1") (pin "1") (pinfunction "(OC0B)PG5_1") (pintype "bidirectional"))
      (node (ref "MIC3") (pin "P$2") (pinfunction "P$2_P$2") (pintype "bidirectional"))
    )
    (net (code "62") (name "/S12") (class "Default")
      (node (ref "IC2") (pin "1") (pinfunction "(OC0B)PG5_1") (pintype "bidirectional"))
      (node (ref "MIC6") (pin "P$2") (pinfunction "P$2_P$2") (pintype "bidirectional"))
    )
    (net (code "63") (name "/S13") (class "Default")
      (node (ref "IC3") (pin "1") (pinfunction "(OC0B)PG5_1") (pintype "bidirectional"))
      (node (ref "MIC7") (pin "P$2") (pinfunction "P$2_P$2") (pintype "bidirectional"))
    )
    (net (code "64") (name "/S21") (class "Default")
      (node (ref "IC1") (pin "5") (pinfunction "(OC3A/AIN1)PE3_5") (pintype "bidirectional"))
      (node (ref "MIC3") (pin "P$5") (pinfunction "P$5_P$5") (pintype "bidirectional"))
    )
    (net (code "65") (name "/S22") (class "Default")
      (node (ref "IC2") (pin "5") (pinfunction "(OC3A/AIN1)PE3_5") (pintype "bidirectional"))
      (node (ref "MIC6") (pin "P$5") (pinfunction "P$5_P$5") (pintype "bidirectional"))
    )
    (net (code "66") (name "/S23") (class "Default")
      (node (ref "IC3") (pin "5") (pinfunction "(OC3A/AIN1)PE3_5") (pintype "bidirectional"))
      (node (ref "MIC7") (pin "P$5") (pinfunction "P$5_P$5") (pintype "bidirectional"))
    )
    (net (code "67") (name "/S31") (class "Default")
      (node (ref "IC1") (pin "15") (pinfunction "PH3(OC4A)_15") (pintype "bidirectional"))
      (node (ref "MIC2") (pin "P$2") (pinfunction "P$2_P$2") (pintype "bidirectional"))
    )
    (net (code "68") (name "/S32") (class "Default")
      (node (ref "IC2") (pin "15") (pinfunction "PH3(OC4A)_15") (pintype "bidirectional"))
      (node (ref "MIC5") (pin "P$2") (pinfunction "P$2_P$2") (pintype "bidirectional"))
    )
    (net (code "69") (name "/S33") (class "Default")
      (node (ref "IC3") (pin "15") (pinfunction "PH3(OC4A)_15") (pintype "bidirectional"))
      (node (ref "MIC8") (pin "P$2") (pinfunction "P$2_P$2") (pintype "bidirectional"))
    )
    (net (code "70") (name "/S41") (class "Default")
      (node (ref "IC1") (pin "16") (pinfunction "PH4(OC4B)_16") (pintype "bidirectional"))
      (node (ref "MIC2") (pin "P$5") (pinfunction "P$5_P$5") (pintype "bidirectional"))
    )
    (net (code "71") (name "/S42") (class "Default")
      (node (ref "IC2") (pin "16") (pinfunction "PH4(OC4B)_16") (pintype "bidirectional"))
      (node (ref "MIC5") (pin "P$5") (pinfunction "P$5_P$5") (pintype "bidirectional"))
    )
    (net (code "72") (name "/S43") (class "Default")
      (node (ref "IC3") (pin "16") (pinfunction "PH4(OC4B)_16") (pintype "bidirectional"))
      (node (ref "MIC8") (pin "P$5") (pinfunction "P$5_P$5") (pintype "bidirectional"))
    )
    (net (code "73") (name "/S51") (class "Default")
      (node (ref "IC1") (pin "17") (pinfunction "PH5(OC4C)_17") (pintype "bidirectional"))
      (node (ref "MIC1") (pin "P$2") (pinfunction "P$2_P$2") (pintype "bidirectional"))
    )
    (net (code "74") (name "/S52") (class "Default")
      (node (ref "IC2") (pin "17") (pinfunction "PH5(OC4C)_17") (pintype "bidirectional"))
      (node (ref "MIC4") (pin "P$2") (pinfunction "P$2_P$2") (pintype "bidirectional"))
    )
    (net (code "75") (name "/S53") (class "Default")
      (node (ref "IC3") (pin "17") (pinfunction "PH5(OC4C)_17") (pintype "bidirectional"))
      (node (ref "MIC9") (pin "P$2") (pinfunction "P$2_P$2") (pintype "bidirectional"))
    )
    (net (code "76") (name "/S61") (class "Default")
      (node (ref "IC1") (pin "18") (pinfunction "PH6(OC2B)_18") (pintype "bidirectional"))
      (node (ref "MIC1") (pin "P$5") (pinfunction "P$5_P$5") (pintype "bidirectional"))
    )
    (net (code "77") (name "/S62") (class "Default")
      (node (ref "IC2") (pin "18") (pinfunction "PH6(OC2B)_18") (pintype "bidirectional"))
      (node (ref "MIC4") (pin "P$5") (pinfunction "P$5_P$5") (pintype "bidirectional"))
    )
    (net (code "78") (name "/S63") (class "Default")
      (node (ref "IC3") (pin "18") (pinfunction "PH6(OC2B)_18") (pintype "bidirectional"))
      (node (ref "MIC9") (pin "P$5") (pinfunction "P$5_P$5") (pintype "bidirectional"))
    )
    (net (code "79") (name "/SS1") (class "Default")
      (node (ref "IC1") (pin "19") (pinfunction "(SS/PCINT0)PB0_19") (pintype "bidirectional"))
      (node (ref "JP1") (pin "30") (pinfunction "30_30") (pintype "passive"))
    )
    (net (code "80") (name "/SS2") (class "Default")
      (node (ref "IC2") (pin "19") (pinfunction "(SS/PCINT0)PB0_19") (pintype "bidirectional"))
      (node (ref "JP1") (pin "19") (pinfunction "19_19") (pintype "passive"))
    )
    (net (code "81") (name "/SS3") (class "Default")
      (node (ref "IC3") (pin "19") (pinfunction "(SS/PCINT0)PB0_19") (pintype "bidirectional"))
      (node (ref "JP1") (pin "17") (pinfunction "17_17") (pintype "passive"))
    )
    (net (code "82") (name "/TX1") (class "Default")
      (node (ref "IC1") (pin "3") (pinfunction "(TXD0)PE1_3") (pintype "bidirectional"))
      (node (ref "JP1") (pin "11") (pinfunction "11_11") (pintype "passive"))
    )
    (net (code "83") (name "/TX2") (class "Default")
      (node (ref "IC2") (pin "3") (pinfunction "(TXD0)PE1_3") (pintype "bidirectional"))
      (node (ref "JP1") (pin "9") (pinfunction "9_9") (pintype "passive"))
    )
    (net (code "84") (name "/TX3") (class "Default")
      (node (ref "IC3") (pin "3") (pinfunction "(TXD0)PE1_3") (pintype "bidirectional"))
      (node (ref "JP1") (pin "3") (pinfunction "3_3") (pintype "passive"))
    )
    (net (code "85") (name "Net-(C9-Pad1)") (class "Default")
      (node (ref "C9") (pin "1") (pinfunction "1_1") (pintype "passive"))
      (node (ref "S3") (pin "2") (pinfunction "2_2") (pintype "passive"))
    )
    (net (code "86") (name "Net-(C10-Pad1)") (class "Default")
      (node (ref "C10") (pin "1") (pinfunction "1_1") (pintype "passive"))
      (node (ref "S2") (pin "2") (pinfunction "2_2") (pintype "passive"))
    )
    (net (code "87") (name "Net-(C11-Pad1)") (class "Default")
      (node (ref "C11") (pin "1") (pinfunction "1_1") (pintype "passive"))
      (node (ref "S4") (pin "2") (pinfunction "2_2") (pintype "passive"))
    )
    (net (code "88") (name "Net-(D2-PadC)") (class "Default")
      (node (ref "D2") (pin "C") (pinfunction "C_C") (pintype "passive"))
      (node (ref "R3") (pin "1") (pinfunction "1_1") (pintype "passive"))
    )
    (net (code "89") (name "Net-(D3-PadC)") (class "Default")
      (node (ref "D3") (pin "C") (pinfunction "C_C") (pintype "passive"))
      (node (ref "R4") (pin "1") (pinfunction "1_1") (pintype "passive"))
    )
    (net (code "90") (name "Net-(D7-PadC)") (class "Default")
      (node (ref "D7") (pin "C") (pinfunction "C_C") (pintype "passive"))
      (node (ref "R10") (pin "1") (pinfunction "1_1") (pintype "passive"))
    )
    (net (code "91") (name "Net-(D8-PadC)") (class "Default")
      (node (ref "D8") (pin "C") (pinfunction "C_C") (pintype "passive"))
      (node (ref "R11") (pin "1") (pinfunction "1_1") (pintype "passive"))
    )
    (net (code "92") (name "Net-(D9-PadC)") (class "Default")
      (node (ref "D9") (pin "C") (pinfunction "C_C") (pintype "passive"))
      (node (ref "R12") (pin "1") (pinfunction "1_1") (pintype "passive"))
    )
    (net (code "93") (name "Net-(D11-PadC)") (class "Default")
      (node (ref "D11") (pin "C") (pinfunction "C_C") (pintype "passive"))
      (node (ref "R14") (pin "1") (pinfunction "1_1") (pintype "passive"))
    )
    (net (code "94") (name "Net-(D12-PadC)") (class "Default")
      (node (ref "D12") (pin "C") (pinfunction "C_C") (pintype "passive"))
      (node (ref "R15") (pin "1") (pinfunction "1_1") (pintype "passive"))
    )
    (net (code "95") (name "Net-(D13-PadC)") (class "Default")
      (node (ref "D13") (pin "C") (pinfunction "C_C") (pintype "passive"))
      (node (ref "R16") (pin "1") (pinfunction "1_1") (pintype "passive"))
    )
    (net (code "96") (name "Net-(D15-PadC)") (class "Default")
      (node (ref "D15") (pin "C") (pinfunction "C_C") (pintype "passive"))
      (node (ref "R18") (pin "1") (pinfunction "1_1") (pintype "passive"))
    )
    (net (code "97") (name "Net-(D16-PadC)") (class "Default")
      (node (ref "D16") (pin "C") (pinfunction "C_C") (pintype "passive"))
      (node (ref "R19") (pin "1") (pinfunction "1_1") (pintype "passive"))
    )
    (net (code "98") (name "Net-(D17-PadC)") (class "Default")
      (node (ref "D17") (pin "C") (pinfunction "C_C") (pintype "passive"))
      (node (ref "R20") (pin "1") (pinfunction "1_1") (pintype "passive"))
    )
    (net (code "99") (name "Net-(IC1-AREF)") (class "Default")
      (node (ref "C2") (pin "1") (pinfunction "1_1") (pintype "passive"))
      (node (ref "IC1") (pin "98") (pinfunction "AREF_98") (pintype "bidirectional"))
    )
    (net (code "100") (name "Net-(IC1-XTAL1)") (class "Default")
      (node (ref "C18") (pin "2") (pinfunction "2_2") (pintype "passive"))
      (node (ref "IC1") (pin "34") (pinfunction "XTAL1_34") (pintype "input"))
      (node (ref "Y2") (pin "1") (pinfunction "1_1") (pintype "passive"))
    )
    (net (code "101") (name "Net-(IC1-XTAL2)") (class "Default")
      (node (ref "C19") (pin "2") (pinfunction "2_2") (pintype "passive"))
      (node (ref "IC1") (pin "33") (pinfunction "XTAL2_33") (pintype "output"))
      (node (ref "Y2") (pin "3") (pinfunction "2_3") (pintype "passive"))
    )
    (net (code "102") (name "Net-(IC2-AREF)") (class "Default")
      (node (ref "C14") (pin "1") (pinfunction "1_1") (pintype "passive"))
      (node (ref "IC2") (pin "98") (pinfunction "AREF_98") (pintype "bidirectional"))
    )
    (net (code "103") (name "Net-(IC2-XTAL1)") (class "Default")
      (node (ref "C16") (pin "2") (pinfunction "2_2") (pintype "passive"))
      (node (ref "IC2") (pin "34") (pinfunction "XTAL1_34") (pintype "input"))
      (node (ref "Y3") (pin "1") (pinfunction "1_1") (pintype "passive"))
    )
    (net (code "104") (name "Net-(IC2-XTAL2)") (class "Default")
      (node (ref "C17") (pin "2") (pinfunction "2_2") (pintype "passive"))
      (node (ref "IC2") (pin "33") (pinfunction "XTAL2_33") (pintype "output"))
      (node (ref "Y3") (pin "3") (pinfunction "2_3") (pintype "passive"))
    )
    (net (code "105") (name "Net-(IC3-AREF)") (class "Default")
      (node (ref "C3") (pin "1") (pinfunction "1_1") (pintype "passive"))
      (node (ref "IC3") (pin "98") (pinfunction "AREF_98") (pintype "bidirectional"))
    )
    (net (code "106") (name "Net-(IC3-XTAL1)") (class "Default")
      (node (ref "C12") (pin "2") (pinfunction "2_2") (pintype "passive"))
      (node (ref "IC3") (pin "34") (pinfunction "XTAL1_34") (pintype "input"))
      (node (ref "Y4") (pin "1") (pinfunction "1_1") (pintype "passive"))
    )
    (net (code "107") (name "Net-(IC3-XTAL2)") (class "Default")
      (node (ref "C13") (pin "2") (pinfunction "2_2") (pintype "passive"))
      (node (ref "IC3") (pin "33") (pinfunction "XTAL2_33") (pintype "output"))
      (node (ref "Y4") (pin "3") (pinfunction "2_3") (pintype "passive"))
    )
    (net (code "108") (name "Net-(IC4-FILTER)") (class "Default")
      (node (ref "C8") (pin "1") (pinfunction "1_1") (pintype "passive"))
      (node (ref "IC4") (pin "6") (pinfunction "FILTER_6") (pintype "bidirectional"))
    )
    (net (code "109") (name "Net-(IC5-FILTER)") (class "Default")
      (node (ref "C23") (pin "1") (pinfunction "1_1") (pintype "passive"))
      (node (ref "IC5") (pin "6") (pinfunction "FILTER_6") (pintype "bidirectional"))
    )
    (net (code "110") (name "Net-(IC6-FILTER)") (class "Default")
      (node (ref "C24") (pin "1") (pinfunction "1_1") (pintype "passive"))
      (node (ref "IC6") (pin "6") (pinfunction "FILTER_6") (pintype "bidirectional"))
    )
    (net (code "111") (name "unconnected-(FRC1-Pad2)") (class "Default")
      (node (ref "FRC1") (pin "2") (pinfunction "2_2") (pintype "passive"))
    )
    (net (code "112") (name "unconnected-(FRC1-Pad3)") (class "Default")
      (node (ref "FRC1") (pin "3") (pinfunction "3_3") (pintype "passive"))
    )
    (net (code "113") (name "unconnected-(FRC1-Pad6)") (class "Default")
      (node (ref "FRC1") (pin "6") (pinfunction "6_6") (pintype "passive"))
    )
    (net (code "114") (name "unconnected-(FRC1-Pad8)") (class "Default")
      (node (ref "FRC1") (pin "8") (pinfunction "8_8") (pintype "passive"))
    )
    (net (code "115") (name "unconnected-(FRC1-Pad9)") (class "Default")
      (node (ref "FRC1") (pin "9") (pinfunction "9_9") (pintype "passive"))
    )
    (net (code "116") (name "unconnected-(FRC1-Pad10)") (class "Default")
      (node (ref "FRC1") (pin "10") (pinfunction "10_10") (pintype "passive"))
    )
    (net (code "117") (name "unconnected-(FRC2-Pad2)") (class "Default")
      (node (ref "FRC2") (pin "2") (pinfunction "2_2") (pintype "passive"))
    )
    (net (code "118") (name "unconnected-(FRC2-Pad3)") (class "Default")
      (node (ref "FRC2") (pin "3") (pinfunction "3_3") (pintype "passive"))
    )
    (net (code "119") (name "unconnected-(FRC2-Pad6)") (class "Default")
      (node (ref "FRC2") (pin "6") (pinfunction "6_6") (pintype "passive"))
    )
    (net (code "120") (name "unconnected-(FRC2-Pad8)") (class "Default")
      (node (ref "FRC2") (pin "8") (pinfunction "8_8") (pintype "passive"))
    )
    (net (code "121") (name "unconnected-(FRC2-Pad9)") (class "Default")
      (node (ref "FRC2") (pin "9") (pinfunction "9_9") (pintype "passive"))
    )
    (net (code "122") (name "unconnected-(FRC2-Pad10)") (class "Default")
      (node (ref "FRC2") (pin "10") (pinfunction "10_10") (pintype "passive"))
    )
    (net (code "123") (name "unconnected-(FRC3-Pad2)") (class "Default")
      (node (ref "FRC3") (pin "2") (pinfunction "2_2") (pintype "passive"))
    )
    (net (code "124") (name "unconnected-(FRC3-Pad3)") (class "Default")
      (node (ref "FRC3") (pin "3") (pinfunction "3_3") (pintype "passive"))
    )
    (net (code "125") (name "unconnected-(FRC3-Pad6)") (class "Default")
      (node (ref "FRC3") (pin "6") (pinfunction "6_6") (pintype "passive"))
    )
    (net (code "126") (name "unconnected-(FRC3-Pad8)") (class "Default")
      (node (ref "FRC3") (pin "8") (pinfunction "8_8") (pintype "passive"))
    )
    (net (code "127") (name "unconnected-(FRC3-Pad9)") (class "Default")
      (node (ref "FRC3") (pin "9") (pinfunction "9_9") (pintype "passive"))
    )
    (net (code "128") (name "unconnected-(FRC3-Pad10)") (class "Default")
      (node (ref "FRC3") (pin "10") (pinfunction "10_10") (pintype "passive"))
    )
    (net (code "129") (name "unconnected-(IC1-(A8)PC0-Pad53)") (class "Default")
      (node (ref "IC1") (pin "53") (pinfunction "(A8)PC0_53") (pintype "bidirectional"))
    )
    (net (code "130") (name "unconnected-(IC1-(A9)PC1-Pad54)") (class "Default")
      (node (ref "IC1") (pin "54") (pinfunction "(A9)PC1_54") (pintype "bidirectional"))
    )
    (net (code "131") (name "unconnected-(IC1-(A10)PC2-Pad55)") (class "Default")
      (node (ref "IC1") (pin "55") (pinfunction "(A10)PC2_55") (pintype "bidirectional"))
    )
    (net (code "132") (name "unconnected-(IC1-(A11)PC3-Pad56)") (class "Default")
      (node (ref "IC1") (pin "56") (pinfunction "(A11)PC3_56") (pintype "bidirectional"))
    )
    (net (code "133") (name "unconnected-(IC1-(A12)PC4-Pad57)") (class "Default")
      (node (ref "IC1") (pin "57") (pinfunction "(A12)PC4_57") (pintype "bidirectional"))
    )
    (net (code "134") (name "unconnected-(IC1-(A13)PC5-Pad58)") (class "Default")
      (node (ref "IC1") (pin "58") (pinfunction "(A13)PC5_58") (pintype "bidirectional"))
    )
    (net (code "135") (name "unconnected-(IC1-(A14)PC6-Pad59)") (class "Default")
      (node (ref "IC1") (pin "59") (pinfunction "(A14)PC6_59") (pintype "bidirectional"))
    )
    (net (code "136") (name "unconnected-(IC1-(A15)PC7-Pad60)") (class "Default")
      (node (ref "IC1") (pin "60") (pinfunction "(A15)PC7_60") (pintype "bidirectional"))
    )
    (net (code "137") (name "unconnected-(IC1-(AD0)PA0-Pad78)") (class "Default")
      (node (ref "IC1") (pin "78") (pinfunction "(AD0)PA0_78") (pintype "bidirectional"))
    )
    (net (code "138") (name "unconnected-(IC1-(AD1)PA1-Pad77)") (class "Default")
      (node (ref "IC1") (pin "77") (pinfunction "(AD1)PA1_77") (pintype "bidirectional"))
    )
    (net (code "139") (name "unconnected-(IC1-(AD2)PA2-Pad76)") (class "Default")
      (node (ref "IC1") (pin "76") (pinfunction "(AD2)PA2_76") (pintype "bidirectional"))
    )
    (net (code "140") (name "unconnected-(IC1-(AD3)PA3-Pad75)") (class "Default")
      (node (ref "IC1") (pin "75") (pinfunction "(AD3)PA3_75") (pintype "bidirectional"))
    )
    (net (code "141") (name "unconnected-(IC1-(AD4)PA4-Pad74)") (class "Default")
      (node (ref "IC1") (pin "74") (pinfunction "(AD4)PA4_74") (pintype "bidirectional"))
    )
    (net (code "142") (name "unconnected-(IC1-(AD5)PA5-Pad73)") (class "Default")
      (node (ref "IC1") (pin "73") (pinfunction "(AD5)PA5_73") (pintype "bidirectional"))
    )
    (net (code "143") (name "unconnected-(IC1-(AD6)PA6-Pad72)") (class "Default")
      (node (ref "IC1") (pin "72") (pinfunction "(AD6)PA6_72") (pintype "bidirectional"))
    )
    (net (code "144") (name "unconnected-(IC1-(AD7)PA7-Pad71)") (class "Default")
      (node (ref "IC1") (pin "71") (pinfunction "(AD7)PA7_71") (pintype "bidirectional"))
    )
    (net (code "145") (name "unconnected-(IC1-(ADC1)PF1-Pad96)") (class "Default")
      (node (ref "IC1") (pin "96") (pinfunction "(ADC1)PF1_96") (pintype "bidirectional"))
    )
    (net (code "146") (name "unconnected-(IC1-(ADC2)PF2-Pad95)") (class "Default")
      (node (ref "IC1") (pin "95") (pinfunction "(ADC2)PF2_95") (pintype "bidirectional"))
    )
    (net (code "147") (name "unconnected-(IC1-(ADC3)PF3-Pad94)") (class "Default")
      (node (ref "IC1") (pin "94") (pinfunction "(ADC3)PF3_94") (pintype "bidirectional"))
    )
    (net (code "148") (name "unconnected-(IC1-(ADC4{slash}TCK)PF4-Pad93)") (class "Default")
      (node (ref "IC1") (pin "93") (pinfunction "(ADC4/TCK)PF4_93") (pintype "bidirectional"))
    )
    (net (code "149") (name "unconnected-(IC1-(ADC5{slash}TMS)PF5-Pad92)") (class "Default")
      (node (ref "IC1") (pin "92") (pinfunction "(ADC5/TMS)PF5_92") (pintype "bidirectional"))
    )
    (net (code "150") (name "unconnected-(IC1-(ADC6{slash}TDO)PF6-Pad91)") (class "Default")
      (node (ref "IC1") (pin "91") (pinfunction "(ADC6/TDO)PF6_91") (pintype "bidirectional"))
    )
    (net (code "151") (name "unconnected-(IC1-(ADC7{slash}TDI)PF7-Pad90)") (class "Default")
      (node (ref "IC1") (pin "90") (pinfunction "(ADC7/TDI)PF7_90") (pintype "bidirectional"))
    )
    (net (code "152") (name "unconnected-(IC1-(ALE)PG2-Pad70)") (class "Default")
      (node (ref "IC1") (pin "70") (pinfunction "(ALE)PG2_70") (pintype "bidirectional"))
    )
    (net (code "153") (name "unconnected-(IC1-(CLKO{slash}ICP3{slash}INT7)PE7-Pad9)") (class "Default")
      (node (ref "IC1") (pin "9") (pinfunction "(CLKO/ICP3/INT7)PE7_9") (pintype "bidirectional"))
    )
    (net (code "154") (name "unconnected-(IC1-(ICP1)PD4-Pad47)") (class "Default")
      (node (ref "IC1") (pin "47") (pinfunction "(ICP1)PD4_47") (pintype "bidirectional"))
    )
    (net (code "155") (name "unconnected-(IC1-(OC0A{slash}OC1C{slash}PCINT7)PB7-Pad26)") (class "Default")
      (node (ref "IC1") (pin "26") (pinfunction "(OC0A/OC1C/PCINT7)PB7_26") (pintype "bidirectional"))
    )
    (net (code "156") (name "unconnected-(IC1-(OC3B{slash}INT4)PE4-Pad6)") (class "Default")
      (node (ref "IC1") (pin "6") (pinfunction "(OC3B/INT4)PE4_6") (pintype "bidirectional"))
    )
    (net (code "157") (name "unconnected-(IC1-(RD)PG1-Pad52)") (class "Default")
      (node (ref "IC1") (pin "52") (pinfunction "(RD)PG1_52") (pintype "bidirectional"))
    )
    (net (code "158") (name "unconnected-(IC1-(T0)PD7-Pad50)") (class "Default")
      (node (ref "IC1") (pin "50") (pinfunction "(T0)PD7_50") (pintype "bidirectional"))
    )
    (net (code "159") (name "unconnected-(IC1-(T1)PD6-Pad49)") (class "Default")
      (node (ref "IC1") (pin "49") (pinfunction "(T1)PD6_49") (pintype "bidirectional"))
    )
    (net (code "160") (name "unconnected-(IC1-(T3{slash}INT6)PE6-Pad8)") (class "Default")
      (node (ref "IC1") (pin "8") (pinfunction "(T3/INT6)PE6_8") (pintype "bidirectional"))
    )
    (net (code "161") (name "unconnected-(IC1-(TOSC1)PG4-Pad29)") (class "Default")
      (node (ref "IC1") (pin "29") (pinfunction "(TOSC1)PG4_29") (pintype "bidirectional"))
    )
    (net (code "162") (name "unconnected-(IC1-(TOSC2)PG3-Pad28)") (class "Default")
      (node (ref "IC1") (pin "28") (pinfunction "(TOSC2)PG3_28") (pintype "bidirectional"))
    )
    (net (code "163") (name "unconnected-(IC1-(WR)PG0-Pad51)") (class "Default")
      (node (ref "IC1") (pin "51") (pinfunction "(WR)PG0_51") (pintype "bidirectional"))
    )
    (net (code "164") (name "unconnected-(IC1-(XCK0{slash}AIN0)PE2-Pad4)") (class "Default")
      (node (ref "IC1") (pin "4") (pinfunction "(XCK0/AIN0)PE2_4") (pintype "bidirectional"))
    )
    (net (code "165") (name "unconnected-(IC1-(XCK1)PD5-Pad48)") (class "Default")
      (node (ref "IC1") (pin "48") (pinfunction "(XCK1)PD5_48") (pintype "bidirectional"))
    )
    (net (code "166") (name "unconnected-(IC1-PH0(RXD2)-Pad12)") (class "Default")
      (node (ref "IC1") (pin "12") (pinfunction "PH0(RXD2)_12") (pintype "bidirectional"))
    )
    (net (code "167") (name "unconnected-(IC1-PH1(TXD2)-Pad13)") (class "Default")
      (node (ref "IC1") (pin "13") (pinfunction "PH1(TXD2)_13") (pintype "bidirectional"))
    )
    (net (code "168") (name "unconnected-(IC1-PH2(XCK2)-Pad14)") (class "Default")
      (node (ref "IC1") (pin "14") (pinfunction "PH2(XCK2)_14") (pintype "bidirectional"))
    )
    (net (code "169") (name "unconnected-(IC1-PH7(T4)-Pad27)") (class "Default")
      (node (ref "IC1") (pin "27") (pinfunction "PH7(T4)_27") (pintype "bidirectional"))
    )
    (net (code "170") (name "unconnected-(IC1-PJ0(RXD3{slash}PCINT9)-Pad63)") (class "Default")
      (node (ref "IC1") (pin "63") (pinfunction "PJ0(RXD3/PCINT9)_63") (pintype "bidirectional"))
    )
    (net (code "171") (name "unconnected-(IC1-PJ1(TXD3{slash}PCINT10)-Pad64)") (class "Default")
      (node (ref "IC1") (pin "64") (pinfunction "PJ1(TXD3/PCINT10)_64") (pintype "bidirectional"))
    )
    (net (code "172") (name "unconnected-(IC1-PJ2(XCK3{slash}PCINT11)-Pad65)") (class "Default")
      (node (ref "IC1") (pin "65") (pinfunction "PJ2(XCK3/PCINT11)_65") (pintype "bidirectional"))
    )
    (net (code "173") (name "unconnected-(IC1-PJ3(PCINT12)-Pad66)") (class "Default")
      (node (ref "IC1") (pin "66") (pinfunction "PJ3(PCINT12)_66") (pintype "bidirectional"))
    )
    (net (code "174") (name "unconnected-(IC1-PJ4(PCINT13)-Pad67)") (class "Default")
      (node (ref "IC1") (pin "67") (pinfunction "PJ4(PCINT13)_67") (pintype "bidirectional"))
    )
    (net (code "175") (name "unconnected-(IC1-PJ5(PCINT14)-Pad68)") (class "Default")
      (node (ref "IC1") (pin "68") (pinfunction "PJ5(PCINT14)_68") (pintype "bidirectional"))
    )
    (net (code "176") (name "unconnected-(IC1-PJ6(PCINT15)-Pad69)") (class "Default")
      (node (ref "IC1") (pin "69") (pinfunction "PJ6(PCINT15)_69") (pintype "bidirectional"))
    )
    (net (code "177") (name "unconnected-(IC1-PJ7-Pad79)") (class "Default")
      (node (ref "IC1") (pin "79") (pinfunction "PJ7_79") (pintype "bidirectional"))
    )
    (net (code "178") (name "unconnected-(IC1-PK0(ADC8{slash}PCINT16)-Pad89)") (class "Default")
      (node (ref "IC1") (pin "89") (pinfunction "PK0(ADC8/PCINT16)_89") (pintype "bidirectional"))
    )
    (net (code "179") (name "unconnected-(IC1-PK1(ADC9{slash}PCINT17)-Pad88)") (class "Default")
      (node (ref "IC1") (pin "88") (pinfunction "PK1(ADC9/PCINT17)_88") (pintype "bidirectional"))
    )
    (net (code "180") (name "unconnected-(IC1-PK2(ADC10{slash}PCINT18)-Pad87)") (class "Default")
      (node (ref "IC1") (pin "87") (pinfunction "PK2(ADC10/PCINT18)_87") (pintype "bidirectional"))
    )
    (net (code "181") (name "unconnected-(IC1-PK3(ADC11{slash}PCINT19)-Pad86)") (class "Default")
      (node (ref "IC1") (pin "86") (pinfunction "PK3(ADC11/PCINT19)_86") (pintype "bidirectional"))
    )
    (net (code "182") (name "unconnected-(IC1-PK4(ADC12{slash}PCINT20)-Pad85)") (class "Default")
      (node (ref "IC1") (pin "85") (pinfunction "PK4(ADC12/PCINT20)_85") (pintype "bidirectional"))
    )
    (net (code "183") (name "unconnected-(IC1-PK5(ADC13{slash}PCINT21)-Pad84)") (class "Default")
      (node (ref "IC1") (pin "84") (pinfunction "PK5(ADC13/PCINT21)_84") (pintype "bidirectional"))
    )
    (net (code "184") (name "unconnected-(IC1-PK6(ADC14{slash}PCINT22)-Pad83)") (class "Default")
      (node (ref "IC1") (pin "83") (pinfunction "PK6(ADC14/PCINT22)_83") (pintype "bidirectional"))
    )
    (net (code "185") (name "unconnected-(IC1-PK7(ADC15{slash}PCINT23)-Pad82)") (class "Default")
      (node (ref "IC1") (pin "82") (pinfunction "PK7(ADC15/PCINT23)_82") (pintype "bidirectional"))
    )
    (net (code "186") (name "unconnected-(IC1-PL0(ICP4)-Pad35)") (class "Default")
      (node (ref "IC1") (pin "35") (pinfunction "PL0(ICP4)_35") (pintype "bidirectional"))
    )
    (net (code "187") (name "unconnected-(IC1-PL1(ICP5)-Pad36)") (class "Default")
      (node (ref "IC1") (pin "36") (pinfunction "PL1(ICP5)_36") (pintype "bidirectional"))
    )
    (net (code "188") (name "unconnected-(IC1-PL2(T5)-Pad37)") (class "Default")
      (node (ref "IC1") (pin "37") (pinfunction "PL2(T5)_37") (pintype "bidirectional"))
    )
    (net (code "189") (name "unconnected-(IC1-PL3(OC5A)-Pad38)") (class "Default")
      (node (ref "IC1") (pin "38") (pinfunction "PL3(OC5A)_38") (pintype "bidirectional"))
    )
    (net (code "190") (name "unconnected-(IC1-PL4(OC5B)-Pad39)") (class "Default")
      (node (ref "IC1") (pin "39") (pinfunction "PL4(OC5B)_39") (pintype "bidirectional"))
    )
    (net (code "191") (name "unconnected-(IC1-PL5(OC5C)-Pad40)") (class "Default")
      (node (ref "IC1") (pin "40") (pinfunction "PL5(OC5C)_40") (pintype "bidirectional"))
    )
    (net (code "192") (name "unconnected-(IC1-PL6-Pad41)") (class "Default")
      (node (ref "IC1") (pin "41") (pinfunction "PL6_41") (pintype "bidirectional"))
    )
    (net (code "193") (name "unconnected-(IC1-PL7-Pad42)") (class "Default")
      (node (ref "IC1") (pin "42") (pinfunction "PL7_42") (pintype "bidirectional"))
    )
    (net (code "194") (name "unconnected-(IC2-(A8)PC0-Pad53)") (class "Default")
      (node (ref "IC2") (pin "53") (pinfunction "(A8)PC0_53") (pintype "bidirectional"))
    )
    (net (code "195") (name "unconnected-(IC2-(A9)PC1-Pad54)") (class "Default")
      (node (ref "IC2") (pin "54") (pinfunction "(A9)PC1_54") (pintype "bidirectional"))
    )
    (net (code "196") (name "unconnected-(IC2-(A10)PC2-Pad55)") (class "Default")
      (node (ref "IC2") (pin "55") (pinfunction "(A10)PC2_55") (pintype "bidirectional"))
    )
    (net (code "197") (name "unconnected-(IC2-(A11)PC3-Pad56)") (class "Default")
      (node (ref "IC2") (pin "56") (pinfunction "(A11)PC3_56") (pintype "bidirectional"))
    )
    (net (code "198") (name "unconnected-(IC2-(A12)PC4-Pad57)") (class "Default")
      (node (ref "IC2") (pin "57") (pinfunction "(A12)PC4_57") (pintype "bidirectional"))
    )
    (net (code "199") (name "unconnected-(IC2-(A13)PC5-Pad58)") (class "Default")
      (node (ref "IC2") (pin "58") (pinfunction "(A13)PC5_58") (pintype "bidirectional"))
    )
    (net (code "200") (name "unconnected-(IC2-(A14)PC6-Pad59)") (class "Default")
      (node (ref "IC2") (pin "59") (pinfunction "(A14)PC6_59") (pintype "bidirectional"))
    )
    (net (code "201") (name "unconnected-(IC2-(A15)PC7-Pad60)") (class "Default")
      (node (ref "IC2") (pin "60") (pinfunction "(A15)PC7_60") (pintype "bidirectional"))
    )
    (net (code "202") (name "unconnected-(IC2-(AD0)PA0-Pad78)") (class "Default")
      (node (ref "IC2") (pin "78") (pinfunction "(AD0)PA0_78") (pintype "bidirectional"))
    )
    (net (code "203") (name "unconnected-(IC2-(AD1)PA1-Pad77)") (class "Default")
      (node (ref "IC2") (pin "77") (pinfunction "(AD1)PA1_77") (pintype "bidirectional"))
    )
    (net (code "204") (name "unconnected-(IC2-(AD2)PA2-Pad76)") (class "Default")
      (node (ref "IC2") (pin "76") (pinfunction "(AD2)PA2_76") (pintype "bidirectional"))
    )
    (net (code "205") (name "unconnected-(IC2-(AD3)PA3-Pad75)") (class "Default")
      (node (ref "IC2") (pin "75") (pinfunction "(AD3)PA3_75") (pintype "bidirectional"))
    )
    (net (code "206") (name "unconnected-(IC2-(AD4)PA4-Pad74)") (class "Default")
      (node (ref "IC2") (pin "74") (pinfunction "(AD4)PA4_74") (pintype "bidirectional"))
    )
    (net (code "207") (name "unconnected-(IC2-(AD5)PA5-Pad73)") (class "Default")
      (node (ref "IC2") (pin "73") (pinfunction "(AD5)PA5_73") (pintype "bidirectional"))
    )
    (net (code "208") (name "unconnected-(IC2-(AD6)PA6-Pad72)") (class "Default")
      (node (ref "IC2") (pin "72") (pinfunction "(AD6)PA6_72") (pintype "bidirectional"))
    )
    (net (code "209") (name "unconnected-(IC2-(AD7)PA7-Pad71)") (class "Default")
      (node (ref "IC2") (pin "71") (pinfunction "(AD7)PA7_71") (pintype "bidirectional"))
    )
    (net (code "210") (name "unconnected-(IC2-(ADC1)PF1-Pad96)") (class "Default")
      (node (ref "IC2") (pin "96") (pinfunction "(ADC1)PF1_96") (pintype "bidirectional"))
    )
    (net (code "211") (name "unconnected-(IC2-(ADC2)PF2-Pad95)") (class "Default")
      (node (ref "IC2") (pin "95") (pinfunction "(ADC2)PF2_95") (pintype "bidirectional"))
    )
    (net (code "212") (name "unconnected-(IC2-(ADC3)PF3-Pad94)") (class "Default")
      (node (ref "IC2") (pin "94") (pinfunction "(ADC3)PF3_94") (pintype "bidirectional"))
    )
    (net (code "213") (name "unconnected-(IC2-(ADC4{slash}TCK)PF4-Pad93)") (class "Default")
      (node (ref "IC2") (pin "93") (pinfunction "(ADC4/TCK)PF4_93") (pintype "bidirectional"))
    )
    (net (code "214") (name "unconnected-(IC2-(ADC5{slash}TMS)PF5-Pad92)") (class "Default")
      (node (ref "IC2") (pin "92") (pinfunction "(ADC5/TMS)PF5_92") (pintype "bidirectional"))
    )
    (net (code "215") (name "unconnected-(IC2-(ADC6{slash}TDO)PF6-Pad91)") (class "Default")
      (node (ref "IC2") (pin "91") (pinfunction "(ADC6/TDO)PF6_91") (pintype "bidirectional"))
    )
    (net (code "216") (name "unconnected-(IC2-(ADC7{slash}TDI)PF7-Pad90)") (class "Default")
      (node (ref "IC2") (pin "90") (pinfunction "(ADC7/TDI)PF7_90") (pintype "bidirectional"))
    )
    (net (code "217") (name "unconnected-(IC2-(ALE)PG2-Pad70)") (class "Default")
      (node (ref "IC2") (pin "70") (pinfunction "(ALE)PG2_70") (pintype "bidirectional"))
    )
    (net (code "218") (name "unconnected-(IC2-(CLKO{slash}ICP3{slash}INT7)PE7-Pad9)") (class "Default")
      (node (ref "IC2") (pin "9") (pinfunction "(CLKO/ICP3/INT7)PE7_9") (pintype "bidirectional"))
    )
    (net (code "219") (name "unconnected-(IC2-(ICP1)PD4-Pad47)") (class "Default")
      (node (ref "IC2") (pin "47") (pinfunction "(ICP1)PD4_47") (pintype "bidirectional"))
    )
    (net (code "220") (name "unconnected-(IC2-(OC0A{slash}OC1C{slash}PCINT7)PB7-Pad26)") (class "Default")
      (node (ref "IC2") (pin "26") (pinfunction "(OC0A/OC1C/PCINT7)PB7_26") (pintype "bidirectional"))
    )
    (net (code "221") (name "unconnected-(IC2-(OC3B{slash}INT4)PE4-Pad6)") (class "Default")
      (node (ref "IC2") (pin "6") (pinfunction "(OC3B/INT4)PE4_6") (pintype "bidirectional"))
    )
    (net (code "222") (name "unconnected-(IC2-(RD)PG1-Pad52)") (class "Default")
      (node (ref "IC2") (pin "52") (pinfunction "(RD)PG1_52") (pintype "bidirectional"))
    )
    (net (code "223") (name "unconnected-(IC2-(T0)PD7-Pad50)") (class "Default")
      (node (ref "IC2") (pin "50") (pinfunction "(T0)PD7_50") (pintype "bidirectional"))
    )
    (net (code "224") (name "unconnected-(IC2-(T1)PD6-Pad49)") (class "Default")
      (node (ref "IC2") (pin "49") (pinfunction "(T1)PD6_49") (pintype "bidirectional"))
    )
    (net (code "225") (name "unconnected-(IC2-(T3{slash}INT6)PE6-Pad8)") (class "Default")
      (node (ref "IC2") (pin "8") (pinfunction "(T3/INT6)PE6_8") (pintype "bidirectional"))
    )
    (net (code "226") (name "unconnected-(IC2-(TOSC1)PG4-Pad29)") (class "Default")
      (node (ref "IC2") (pin "29") (pinfunction "(TOSC1)PG4_29") (pintype "bidirectional"))
    )
    (net (code "227") (name "unconnected-(IC2-(TOSC2)PG3-Pad28)") (class "Default")
      (node (ref "IC2") (pin "28") (pinfunction "(TOSC2)PG3_28") (pintype "bidirectional"))
    )
    (net (code "228") (name "unconnected-(IC2-(WR)PG0-Pad51)") (class "Default")
      (node (ref "IC2") (pin "51") (pinfunction "(WR)PG0_51") (pintype "bidirectional"))
    )
    (net (code "229") (name "unconnected-(IC2-(XCK0{slash}AIN0)PE2-Pad4)") (class "Default")
      (node (ref "IC2") (pin "4") (pinfunction "(XCK0/AIN0)PE2_4") (pintype "bidirectional"))
    )
    (net (code "230") (name "unconnected-(IC2-(XCK1)PD5-Pad48)") (class "Default")
      (node (ref "IC2") (pin "48") (pinfunction "(XCK1)PD5_48") (pintype "bidirectional"))
    )
    (net (code "231") (name "unconnected-(IC2-PH0(RXD2)-Pad12)") (class "Default")
      (node (ref "IC2") (pin "12") (pinfunction "PH0(RXD2)_12") (pintype "bidirectional"))
    )
    (net (code "232") (name "unconnected-(IC2-PH1(TXD2)-Pad13)") (class "Default")
      (node (ref "IC2") (pin "13") (pinfunction "PH1(TXD2)_13") (pintype "bidirectional"))
    )
    (net (code "233") (name "unconnected-(IC2-PH2(XCK2)-Pad14)") (class "Default")
      (node (ref "IC2") (pin "14") (pinfunction "PH2(XCK2)_14") (pintype "bidirectional"))
    )
    (net (code "234") (name "unconnected-(IC2-PH7(T4)-Pad27)") (class "Default")
      (node (ref "IC2") (pin "27") (pinfunction "PH7(T4)_27") (pintype "bidirectional"))
    )
    (net (code "235") (name "unconnected-(IC2-PJ0(RXD3{slash}PCINT9)-Pad63)") (class "Default")
      (node (ref "IC2") (pin "63") (pinfunction "PJ0(RXD3/PCINT9)_63") (pintype "bidirectional"))
    )
    (net (code "236") (name "unconnected-(IC2-PJ1(TXD3{slash}PCINT10)-Pad64)") (class "Default")
      (node (ref "IC2") (pin "64") (pinfunction "PJ1(TXD3/PCINT10)_64") (pintype "bidirectional"))
    )
    (net (code "237") (name "unconnected-(IC2-PJ2(XCK3{slash}PCINT11)-Pad65)") (class "Default")
      (node (ref "IC2") (pin "65") (pinfunction "PJ2(XCK3/PCINT11)_65") (pintype "bidirectional"))
    )
    (net (code "238") (name "unconnected-(IC2-PJ3(PCINT12)-Pad66)") (class "Default")
      (node (ref "IC2") (pin "66") (pinfunction "PJ3(PCINT12)_66") (pintype "bidirectional"))
    )
    (net (code "239") (name "unconnected-(IC2-PJ4(PCINT13)-Pad67)") (class "Default")
      (node (ref "IC2") (pin "67") (pinfunction "PJ4(PCINT13)_67") (pintype "bidirectional"))
    )
    (net (code "240") (name "unconnected-(IC2-PJ5(PCINT14)-Pad68)") (class "Default")
      (node (ref "IC2") (pin "68") (pinfunction "PJ5(PCINT14)_68") (pintype "bidirectional"))
    )
    (net (code "241") (name "unconnected-(IC2-PJ6(PCINT15)-Pad69)") (class "Default")
      (node (ref "IC2") (pin "69") (pinfunction "PJ6(PCINT15)_69") (pintype "bidirectional"))
    )
    (net (code "242") (name "unconnected-(IC2-PJ7-Pad79)") (class "Default")
      (node (ref "IC2") (pin "79") (pinfunction "PJ7_79") (pintype "bidirectional"))
    )
    (net (code "243") (name "unconnected-(IC2-PK0(ADC8{slash}PCINT16)-Pad89)") (class "Default")
      (node (ref "IC2") (pin "89") (pinfunction "PK0(ADC8/PCINT16)_89") (pintype "bidirectional"))
    )
    (net (code "244") (name "unconnected-(IC2-PK1(ADC9{slash}PCINT17)-Pad88)") (class "Default")
      (node (ref "IC2") (pin "88") (pinfunction "PK1(ADC9/PCINT17)_88") (pintype "bidirectional"))
    )
    (net (code "245") (name "unconnected-(IC2-PK2(ADC10{slash}PCINT18)-Pad87)") (class "Default")
      (node (ref "IC2") (pin "87") (pinfunction "PK2(ADC10/PCINT18)_87") (pintype "bidirectional"))
    )
    (net (code "246") (name "unconnected-(IC2-PK3(ADC11{slash}PCINT19)-Pad86)") (class "Default")
      (node (ref "IC2") (pin "86") (pinfunction "PK3(ADC11/PCINT19)_86") (pintype "bidirectional"))
    )
    (net (code "247") (name "unconnected-(IC2-PK4(ADC12{slash}PCINT20)-Pad85)") (class "Default")
      (node (ref "IC2") (pin "85") (pinfunction "PK4(ADC12/PCINT20)_85") (pintype "bidirectional"))
    )
    (net (code "248") (name "unconnected-(IC2-PK5(ADC13{slash}PCINT21)-Pad84)") (class "Default")
      (node (ref "IC2") (pin "84") (pinfunction "PK5(ADC13/PCINT21)_84") (pintype "bidirectional"))
    )
    (net (code "249") (name "unconnected-(IC2-PK6(ADC14{slash}PCINT22)-Pad83)") (class "Default")
      (node (ref "IC2") (pin "83") (pinfunction "PK6(ADC14/PCINT22)_83") (pintype "bidirectional"))
    )
    (net (code "250") (name "unconnected-(IC2-PK7(ADC15{slash}PCINT23)-Pad82)") (class "Default")
      (node (ref "IC2") (pin "82") (pinfunction "PK7(ADC15/PCINT23)_82") (pintype "bidirectional"))
    )
    (net (code "251") (name "unconnected-(IC2-PL0(ICP4)-Pad35)") (class "Default")
      (node (ref "IC2") (pin "35") (pinfunction "PL0(ICP4)_35") (pintype "bidirectional"))
    )
    (net (code "252") (name "unconnected-(IC2-PL1(ICP5)-Pad36)") (class "Default")
      (node (ref "IC2") (pin "36") (pinfunction "PL1(ICP5)_36") (pintype "bidirectional"))
    )
    (net (code "253") (name "unconnected-(IC2-PL2(T5)-Pad37)") (class "Default")
      (node (ref "IC2") (pin "37") (pinfunction "PL2(T5)_37") (pintype "bidirectional"))
    )
    (net (code "254") (name "unconnected-(IC2-PL3(OC5A)-Pad38)") (class "Default")
      (node (ref "IC2") (pin "38") (pinfunction "PL3(OC5A)_38") (pintype "bidirectional"))
    )
    (net (code "255") (name "unconnected-(IC2-PL4(OC5B)-Pad39)") (class "Default")
      (node (ref "IC2") (pin "39") (pinfunction "PL4(OC5B)_39") (pintype "bidirectional"))
    )
    (net (code "256") (name "unconnected-(IC2-PL5(OC5C)-Pad40)") (class "Default")
      (node (ref "IC2") (pin "40") (pinfunction "PL5(OC5C)_40") (pintype "bidirectional"))
    )
    (net (code "257") (name "unconnected-(IC2-PL6-Pad41)") (class "Default")
      (node (ref "IC2") (pin "41") (pinfunction "PL6_41") (pintype "bidirectional"))
    )
    (net (code "258") (name "unconnected-(IC2-PL7-Pad42)") (class "Default")
      (node (ref "IC2") (pin "42") (pinfunction "PL7_42") (pintype "bidirectional"))
    )
    (net (code "259") (name "unconnected-(IC3-(A8)PC0-Pad53)") (class "Default")
      (node (ref "IC3") (pin "53") (pinfunction "(A8)PC0_53") (pintype "bidirectional"))
    )
    (net (code "260") (name "unconnected-(IC3-(A9)PC1-Pad54)") (class "Default")
      (node (ref "IC3") (pin "54") (pinfunction "(A9)PC1_54") (pintype "bidirectional"))
    )
    (net (code "261") (name "unconnected-(IC3-(A10)PC2-Pad55)") (class "Default")
      (node (ref "IC3") (pin "55") (pinfunction "(A10)PC2_55") (pintype "bidirectional"))
    )
    (net (code "262") (name "unconnected-(IC3-(A11)PC3-Pad56)") (class "Default")
      (node (ref "IC3") (pin "56") (pinfunction "(A11)PC3_56") (pintype "bidirectional"))
    )
    (net (code "263") (name "unconnected-(IC3-(A12)PC4-Pad57)") (class "Default")
      (node (ref "IC3") (pin "57") (pinfunction "(A12)PC4_57") (pintype "bidirectional"))
    )
    (net (code "264") (name "unconnected-(IC3-(A13)PC5-Pad58)") (class "Default")
      (node (ref "IC3") (pin "58") (pinfunction "(A13)PC5_58") (pintype "bidirectional"))
    )
    (net (code "265") (name "unconnected-(IC3-(A14)PC6-Pad59)") (class "Default")
      (node (ref "IC3") (pin "59") (pinfunction "(A14)PC6_59") (pintype "bidirectional"))
    )
    (net (code "266") (name "unconnected-(IC3-(A15)PC7-Pad60)") (class "Default")
      (node (ref "IC3") (pin "60") (pinfunction "(A15)PC7_60") (pintype "bidirectional"))
    )
    (net (code "267") (name "unconnected-(IC3-(AD0)PA0-Pad78)") (class "Default")
      (node (ref "IC3") (pin "78") (pinfunction "(AD0)PA0_78") (pintype "bidirectional"))
    )
    (net (code "268") (name "unconnected-(IC3-(AD1)PA1-Pad77)") (class "Default")
      (node (ref "IC3") (pin "77") (pinfunction "(AD1)PA1_77") (pintype "bidirectional"))
    )
    (net (code "269") (name "unconnected-(IC3-(AD2)PA2-Pad76)") (class "Default")
      (node (ref "IC3") (pin "76") (pinfunction "(AD2)PA2_76") (pintype "bidirectional"))
    )
    (net (code "270") (name "unconnected-(IC3-(AD3)PA3-Pad75)") (class "Default")
      (node (ref "IC3") (pin "75") (pinfunction "(AD3)PA3_75") (pintype "bidirectional"))
    )
    (net (code "271") (name "unconnected-(IC3-(AD4)PA4-Pad74)") (class "Default")
      (node (ref "IC3") (pin "74") (pinfunction "(AD4)PA4_74") (pintype "bidirectional"))
    )
    (net (code "272") (name "unconnected-(IC3-(AD5)PA5-Pad73)") (class "Default")
      (node (ref "IC3") (pin "73") (pinfunction "(AD5)PA5_73") (pintype "bidirectional"))
    )
    (net (code "273") (name "unconnected-(IC3-(AD6)PA6-Pad72)") (class "Default")
      (node (ref "IC3") (pin "72") (pinfunction "(AD6)PA6_72") (pintype "bidirectional"))
    )
    (net (code "274") (name "unconnected-(IC3-(AD7)PA7-Pad71)") (class "Default")
      (node (ref "IC3") (pin "71") (pinfunction "(AD7)PA7_71") (pintype "bidirectional"))
    )
    (net (code "275") (name "unconnected-(IC3-(ADC1)PF1-Pad96)") (class "Default")
      (node (ref "IC3") (pin "96") (pinfunction "(ADC1)PF1_96") (pintype "bidirectional"))
    )
    (net (code "276") (name "unconnected-(IC3-(ADC2)PF2-Pad95)") (class "Default")
      (node (ref "IC3") (pin "95") (pinfunction "(ADC2)PF2_95") (pintype "bidirectional"))
    )
    (net (code "277") (name "unconnected-(IC3-(ADC3)PF3-Pad94)") (class "Default")
      (node (ref "IC3") (pin "94") (pinfunction "(ADC3)PF3_94") (pintype "bidirectional"))
    )
    (net (code "278") (name "unconnected-(IC3-(ADC4{slash}TCK)PF4-Pad93)") (class "Default")
      (node (ref "IC3") (pin "93") (pinfunction "(ADC4/TCK)PF4_93") (pintype "bidirectional"))
    )
    (net (code "279") (name "unconnected-(IC3-(ADC5{slash}TMS)PF5-Pad92)") (class "Default")
      (node (ref "IC3") (pin "92") (pinfunction "(ADC5/TMS)PF5_92") (pintype "bidirectional"))
    )
    (net (code "280") (name "unconnected-(IC3-(ADC6{slash}TDO)PF6-Pad91)") (class "Default")
      (node (ref "IC3") (pin "91") (pinfunction "(ADC6/TDO)PF6_91") (pintype "bidirectional"))
    )
    (net (code "281") (name "unconnected-(IC3-(ADC7{slash}TDI)PF7-Pad90)") (class "Default")
      (node (ref "IC3") (pin "90") (pinfunction "(ADC7/TDI)PF7_90") (pintype "bidirectional"))
    )
    (net (code "282") (name "unconnected-(IC3-(ALE)PG2-Pad70)") (class "Default")
      (node (ref "IC3") (pin "70") (pinfunction "(ALE)PG2_70") (pintype "bidirectional"))
    )
    (net (code "283") (name "unconnected-(IC3-(CLKO{slash}ICP3{slash}INT7)PE7-Pad9)") (class "Default")
      (node (ref "IC3") (pin "9") (pinfunction "(CLKO/ICP3/INT7)PE7_9") (pintype "bidirectional"))
    )
    (net (code "284") (name "unconnected-(IC3-(ICP1)PD4-Pad47)") (class "Default")
      (node (ref "IC3") (pin "47") (pinfunction "(ICP1)PD4_47") (pintype "bidirectional"))
    )
    (net (code "285") (name "unconnected-(IC3-(OC0A{slash}OC1C{slash}PCINT7)PB7-Pad26)") (class "Default")
      (node (ref "IC3") (pin "26") (pinfunction "(OC0A/OC1C/PCINT7)PB7_26") (pintype "bidirectional"))
    )
    (net (code "286") (name "unconnected-(IC3-(OC3B{slash}INT4)PE4-Pad6)") (class "Default")
      (node (ref "IC3") (pin "6") (pinfunction "(OC3B/INT4)PE4_6") (pintype "bidirectional"))
    )
    (net (code "287") (name "unconnected-(IC3-(RD)PG1-Pad52)") (class "Default")
      (node (ref "IC3") (pin "52") (pinfunction "(RD)PG1_52") (pintype "bidirectional"))
    )
    (net (code "288") (name "unconnected-(IC3-(T0)PD7-Pad50)") (class "Default")
      (node (ref "IC3") (pin "50") (pinfunction "(T0)PD7_50") (pintype "bidirectional"))
    )
    (net (code "289") (name "unconnected-(IC3-(T1)PD6-Pad49)") (class "Default")
      (node (ref "IC3") (pin "49") (pinfunction "(T1)PD6_49") (pintype "bidirectional"))
    )
    (net (code "290") (name "unconnected-(IC3-(T3{slash}INT6)PE6-Pad8)") (class "Default")
      (node (ref "IC3") (pin "8") (pinfunction "(T3/INT6)PE6_8") (pintype "bidirectional"))
    )
    (net (code "291") (name "unconnected-(IC3-(TOSC1)PG4-Pad29)") (class "Default")
      (node (ref "IC3") (pin "29") (pinfunction "(TOSC1)PG4_29") (pintype "bidirectional"))
    )
    (net (code "292") (name "unconnected-(IC3-(TOSC2)PG3-Pad28)") (class "Default")
      (node (ref "IC3") (pin "28") (pinfunction "(TOSC2)PG3_28") (pintype "bidirectional"))
    )
    (net (code "293") (name "unconnected-(IC3-(WR)PG0-Pad51)") (class "Default")
      (node (ref "IC3") (pin "51") (pinfunction "(WR)PG0_51") (pintype "bidirectional"))
    )
    (net (code "294") (name "unconnected-(IC3-(XCK0{slash}AIN0)PE2-Pad4)") (class "Default")
      (node (ref "IC3") (pin "4") (pinfunction "(XCK0/AIN0)PE2_4") (pintype "bidirectional"))
    )
    (net (code "295") (name "unconnected-(IC3-(XCK1)PD5-Pad48)") (class "Default")
      (node (ref "IC3") (pin "48") (pinfunction "(XCK1)PD5_48") (pintype "bidirectional"))
    )
    (net (code "296") (name "unconnected-(IC3-PH0(RXD2)-Pad12)") (class "Default")
      (node (ref "IC3") (pin "12") (pinfunction "PH0(RXD2)_12") (pintype "bidirectional"))
    )
    (net (code "297") (name "unconnected-(IC3-PH1(TXD2)-Pad13)") (class "Default")
      (node (ref "IC3") (pin "13") (pinfunction "PH1(TXD2)_13") (pintype "bidirectional"))
    )
    (net (code "298") (name "unconnected-(IC3-PH2(XCK2)-Pad14)") (class "Default")
      (node (ref "IC3") (pin "14") (pinfunction "PH2(XCK2)_14") (pintype "bidirectional"))
    )
    (net (code "299") (name "unconnected-(IC3-PH7(T4)-Pad27)") (class "Default")
      (node (ref "IC3") (pin "27") (pinfunction "PH7(T4)_27") (pintype "bidirectional"))
    )
    (net (code "300") (name "unconnected-(IC3-PJ0(RXD3{slash}PCINT9)-Pad63)") (class "Default")
      (node (ref "IC3") (pin "63") (pinfunction "PJ0(RXD3/PCINT9)_63") (pintype "bidirectional"))
    )
    (net (code "301") (name "unconnected-(IC3-PJ1(TXD3{slash}PCINT10)-Pad64)") (class "Default")
      (node (ref "IC3") (pin "64") (pinfunction "PJ1(TXD3/PCINT10)_64") (pintype "bidirectional"))
    )
    (net (code "302") (name "unconnected-(IC3-PJ2(XCK3{slash}PCINT11)-Pad65)") (class "Default")
      (node (ref "IC3") (pin "65") (pinfunction "PJ2(XCK3/PCINT11)_65") (pintype "bidirectional"))
    )
    (net (code "303") (name "unconnected-(IC3-PJ3(PCINT12)-Pad66)") (class "Default")
      (node (ref "IC3") (pin "66") (pinfunction "PJ3(PCINT12)_66") (pintype "bidirectional"))
    )
    (net (code "304") (name "unconnected-(IC3-PJ4(PCINT13)-Pad67)") (class "Default")
      (node (ref "IC3") (pin "67") (pinfunction "PJ4(PCINT13)_67") (pintype "bidirectional"))
    )
    (net (code "305") (name "unconnected-(IC3-PJ5(PCINT14)-Pad68)") (class "Default")
      (node (ref "IC3") (pin "68") (pinfunction "PJ5(PCINT14)_68") (pintype "bidirectional"))
    )
    (net (code "306") (name "unconnected-(IC3-PJ6(PCINT15)-Pad69)") (class "Default")
      (node (ref "IC3") (pin "69") (pinfunction "PJ6(PCINT15)_69") (pintype "bidirectional"))
    )
    (net (code "307") (name "unconnected-(IC3-PJ7-Pad79)") (class "Default")
      (node (ref "IC3") (pin "79") (pinfunction "PJ7_79") (pintype "bidirectional"))
    )
    (net (code "308") (name "unconnected-(IC3-PK0(ADC8{slash}PCINT16)-Pad89)") (class "Default")
      (node (ref "IC3") (pin "89") (pinfunction "PK0(ADC8/PCINT16)_89") (pintype "bidirectional"))
    )
    (net (code "309") (name "unconnected-(IC3-PK1(ADC9{slash}PCINT17)-Pad88)") (class "Default")
      (node (ref "IC3") (pin "88") (pinfunction "PK1(ADC9/PCINT17)_88") (pintype "bidirectional"))
    )
    (net (code "310") (name "unconnected-(IC3-PK2(ADC10{slash}PCINT18)-Pad87)") (class "Default")
      (node (ref "IC3") (pin "87") (pinfunction "PK2(ADC10/PCINT18)_87") (pintype "bidirectional"))
    )
    (net (code "311") (name "unconnected-(IC3-PK3(ADC11{slash}PCINT19)-Pad86)") (class "Default")
      (node (ref "IC3") (pin "86") (pinfunction "PK3(ADC11/PCINT19)_86") (pintype "bidirectional"))
    )
    (net (code "312") (name "unconnected-(IC3-PK4(ADC12{slash}PCINT20)-Pad85)") (class "Default")
      (node (ref "IC3") (pin "85") (pinfunction "PK4(ADC12/PCINT20)_85") (pintype "bidirectional"))
    )
    (net (code "313") (name "unconnected-(IC3-PK5(ADC13{slash}PCINT21)-Pad84)") (class "Default")
      (node (ref "IC3") (pin "84") (pinfunction "PK5(ADC13/PCINT21)_84") (pintype "bidirectional"))
    )
    (net (code "314") (name "unconnected-(IC3-PK6(ADC14{slash}PCINT22)-Pad83)") (class "Default")
      (node (ref "IC3") (pin "83") (pinfunction "PK6(ADC14/PCINT22)_83") (pintype "bidirectional"))
    )
    (net (code "315") (name "unconnected-(IC3-PK7(ADC15{slash}PCINT23)-Pad82)") (class "Default")
      (node (ref "IC3") (pin "82") (pinfunction "PK7(ADC15/PCINT23)_82") (pintype "bidirectional"))
    )
    (net (code "316") (name "unconnected-(IC3-PL0(ICP4)-Pad35)") (class "Default")
      (node (ref "IC3") (pin "35") (pinfunction "PL0(ICP4)_35") (pintype "bidirectional"))
    )
    (net (code "317") (name "unconnected-(IC3-PL1(ICP5)-Pad36)") (class "Default")
      (node (ref "IC3") (pin "36") (pinfunction "PL1(ICP5)_36") (pintype "bidirectional"))
    )
    (net (code "318") (name "unconnected-(IC3-PL2(T5)-Pad37)") (class "Default")
      (node (ref "IC3") (pin "37") (pinfunction "PL2(T5)_37") (pintype "bidirectional"))
    )
    (net (code "319") (name "unconnected-(IC3-PL3(OC5A)-Pad38)") (class "Default")
      (node (ref "IC3") (pin "38") (pinfunction "PL3(OC5A)_38") (pintype "bidirectional"))
    )
    (net (code "320") (name "unconnected-(IC3-PL4(OC5B)-Pad39)") (class "Default")
      (node (ref "IC3") (pin "39") (pinfunction "PL4(OC5B)_39") (pintype "bidirectional"))
    )
    (net (code "321") (name "unconnected-(IC3-PL5(OC5C)-Pad40)") (class "Default")
      (node (ref "IC3") (pin "40") (pinfunction "PL5(OC5C)_40") (pintype "bidirectional"))
    )
    (net (code "322") (name "unconnected-(IC3-PL6-Pad41)") (class "Default")
      (node (ref "IC3") (pin "41") (pinfunction "PL6_41") (pintype "bidirectional"))
    )
    (net (code "323") (name "unconnected-(IC3-PL7-Pad42)") (class "Default")
      (node (ref "IC3") (pin "42") (pinfunction "PL7_42") (pintype "bidirectional"))
    )
    (net (code "324") (name "unconnected-(IC4-I+_1-Pad2)") (class "Default")
      (node (ref "IC4") (pin "2") (pinfunction "I+_1_2") (pintype "bidirectional"))
    )
    (net (code "325") (name "unconnected-(IC4-I-_1-Pad4)") (class "Default")
      (node (ref "IC4") (pin "4") (pinfunction "I-_1_4") (pintype "bidirectional"))
    )
    (net (code "326") (name "unconnected-(IC5-I+_1-Pad2)") (class "Default")
      (node (ref "IC5") (pin "2") (pinfunction "I+_1_2") (pintype "bidirectional"))
    )
    (net (code "327") (name "unconnected-(IC5-I-_1-Pad4)") (class "Default")
      (node (ref "IC5") (pin "4") (pinfunction "I-_1_4") (pintype "bidirectional"))
    )
    (net (code "328") (name "unconnected-(IC6-I+_1-Pad2)") (class "Default")
      (node (ref "IC6") (pin "2") (pinfunction "I+_1_2") (pintype "bidirectional"))
    )
    (net (code "329") (name "unconnected-(IC6-I-_1-Pad4)") (class "Default")
      (node (ref "IC6") (pin "4") (pinfunction "I-_1_4") (pintype "bidirectional"))
    )
    (net (code "330") (name "unconnected-(JP1-Pad13)") (class "Default")
      (node (ref "JP1") (pin "13") (pinfunction "13_13") (pintype "passive"))
    )
    (net (code "331") (name "unconnected-(JP1-Pad14)") (class "Default")
      (node (ref "JP1") (pin "14") (pinfunction "14_14") (pintype "passive"))
    )
    (net (code "332") (name "unconnected-(JP1-Pad15)") (class "Default")
      (node (ref "JP1") (pin "15") (pinfunction "15_15") (pintype "passive"))
    )
    (net (code "333") (name "unconnected-(JP1-Pad16)") (class "Default")
      (node (ref "JP1") (pin "16") (pinfunction "16_16") (pintype "passive"))
    )
    (net (code "334") (name "unconnected-(JP1-Pad18)") (class "Default")
      (node (ref "JP1") (pin "18") (pinfunction "18_18") (pintype "passive"))
    )
    (net (code "335") (name "unconnected-(JP1-Pad20)") (class "Default")
      (node (ref "JP1") (pin "20") (pinfunction "20_20") (pintype "passive"))
    )
    (net (code "336") (name "unconnected-(JP1-Pad21)") (class "Default")
      (node (ref "JP1") (pin "21") (pinfunction "21_21") (pintype "passive"))
    )
    (net (code "337") (name "unconnected-(JP1-Pad22)") (class "Default")
      (node (ref "JP1") (pin "22") (pinfunction "22_22") (pintype "passive"))
    )
    (net (code "338") (name "unconnected-(JP1-Pad24)") (class "Default")
      (node (ref "JP1") (pin "24") (pinfunction "24_24") (pintype "passive"))
    )
    (net (code "339") (name "unconnected-(JP1-Pad26)") (class "Default")
      (node (ref "JP1") (pin "26") (pinfunction "26_26") (pintype "passive"))
    )
  )
)
